# PocketCHIP-v1_0.net
KiCad netlist of a schematic drawn in EAGLE
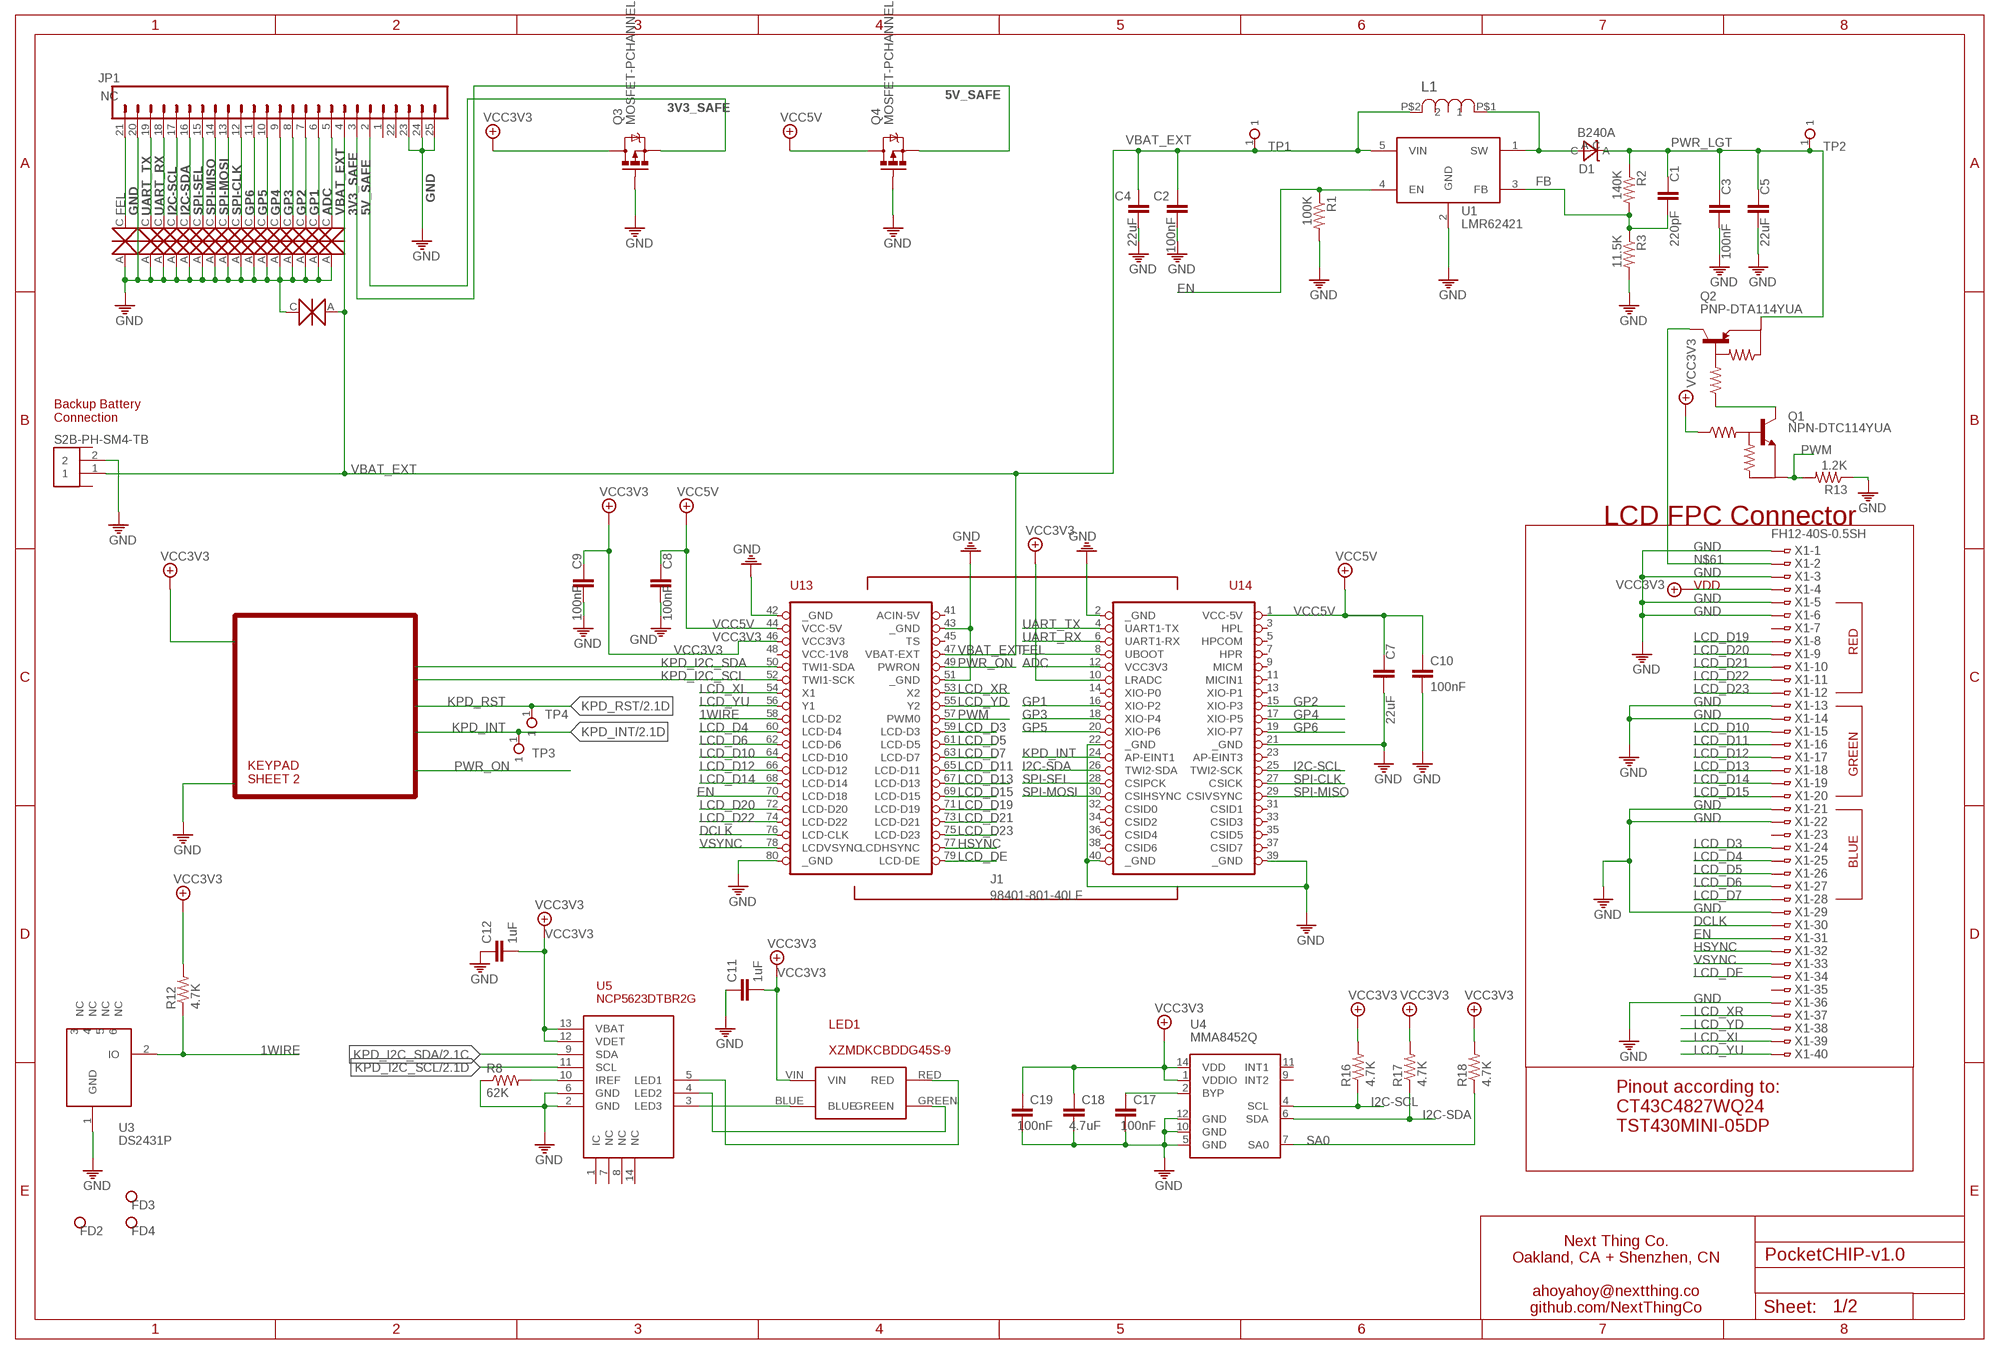
[diagram p0: schematic, sheet 1]
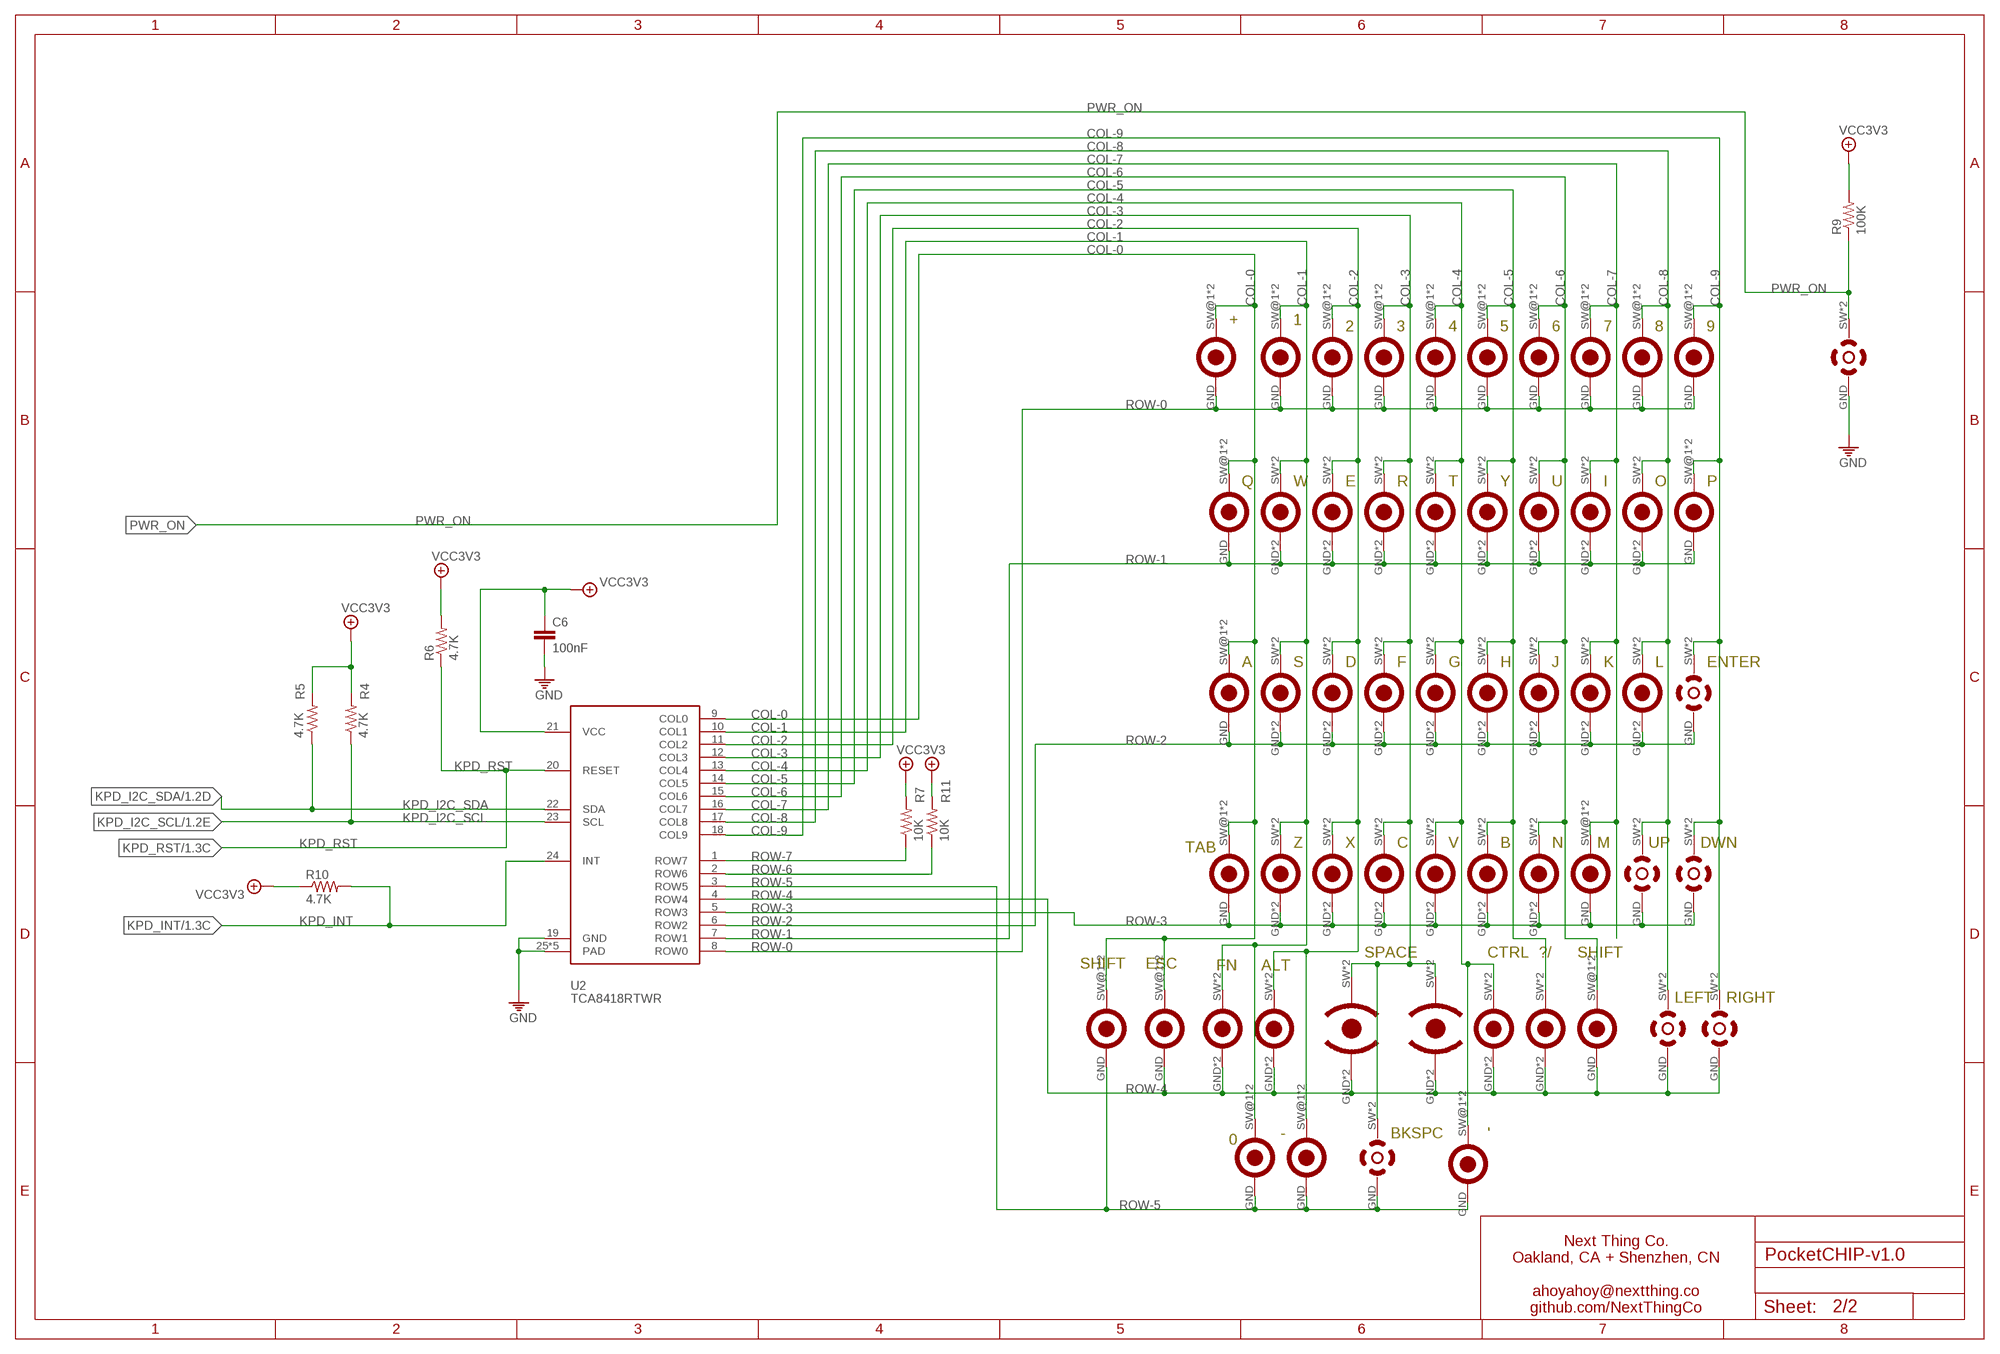
[diagram p1: schematic, sheet 2]

(export (version "E")
  (design (tool "Eeschema 10.0.6"))
  (components
    (comp (ref "'")
      (value "M272201PAD")
      (footprint "eagle-import:SNAPDOME_M27220_1PAD")
      (libsource (lib "eagle-import") (part "M272201PAD"))
    )
    (comp (ref "+")
      (value "M272201PAD")
      (footprint "eagle-import:SNAPDOME_M27220_1PAD")
      (libsource (lib "eagle-import") (part "M272201PAD"))
    )
    (comp (ref "-")
      (value "M272201PAD")
      (footprint "eagle-import:SNAPDOME_M27220_1PAD")
      (libsource (lib "eagle-import") (part "M272201PAD"))
    )
    (comp (ref "0")
      (value "M272201PAD")
      (footprint "eagle-import:SNAPDOME_M27220_1PAD")
      (libsource (lib "eagle-import") (part "M272201PAD"))
    )
    (comp (ref "1")
      (value "M272201PAD")
      (footprint "eagle-import:SNAPDOME_M27220_1PAD")
      (libsource (lib "eagle-import") (part "M272201PAD"))
    )
    (comp (ref "2")
      (value "M272201PAD")
      (footprint "eagle-import:SNAPDOME_M27220_1PAD")
      (libsource (lib "eagle-import") (part "M272201PAD"))
    )
    (comp (ref "3")
      (value "M272201PAD")
      (footprint "eagle-import:SNAPDOME_M27220_1PAD")
      (libsource (lib "eagle-import") (part "M272201PAD"))
    )
    (comp (ref "4")
      (value "M272201PAD")
      (footprint "eagle-import:SNAPDOME_M27220_1PAD")
      (libsource (lib "eagle-import") (part "M272201PAD"))
    )
    (comp (ref "5")
      (value "M272201PAD")
      (footprint "eagle-import:SNAPDOME_M27220_1PAD")
      (libsource (lib "eagle-import") (part "M272201PAD"))
    )
    (comp (ref "6")
      (value "M272201PAD")
      (footprint "eagle-import:SNAPDOME_M27220_1PAD")
      (libsource (lib "eagle-import") (part "M272201PAD"))
    )
    (comp (ref "7")
      (value "M272201PAD")
      (footprint "eagle-import:SNAPDOME_M27220_1PAD")
      (libsource (lib "eagle-import") (part "M272201PAD"))
    )
    (comp (ref "8")
      (value "M272201PAD")
      (footprint "eagle-import:SNAPDOME_M27220_1PAD")
      (libsource (lib "eagle-import") (part "M272201PAD"))
    )
    (comp (ref "9")
      (value "M272201PAD")
      (footprint "eagle-import:SNAPDOME_M27220_1PAD")
      (libsource (lib "eagle-import") (part "M272201PAD"))
    )
    (comp (ref "?/")
      (value "M27220")
      (footprint "eagle-import:SNAPDOME_M27220")
      (libsource (lib "eagle-import") (part "M27220"))
    )
    (comp (ref "A")
      (value "M272201PAD")
      (footprint "eagle-import:SNAPDOME_M27220_1PAD")
      (libsource (lib "eagle-import") (part "M272201PAD"))
    )
    (comp (ref "ALT")
      (value "M27220")
      (footprint "eagle-import:SNAPDOME_M27220")
      (libsource (lib "eagle-import") (part "M27220"))
    )
    (comp (ref "B")
      (value "M27220")
      (footprint "eagle-import:SNAPDOME_M27220")
      (libsource (lib "eagle-import") (part "M27220"))
    )
    (comp (ref "BKSPC")
      (value "BL08260")
      (footprint "eagle-import:SNAPDOME_BL08260")
      (libsource (lib "eagle-import") (part "BL08260"))
    )
    (comp (ref "C")
      (value "M27220")
      (footprint "eagle-import:SNAPDOME_M27220")
      (libsource (lib "eagle-import") (part "M27220"))
    )
    (comp (ref "C6")
      (value "100nF")
      (footprint "eagle-import:C0402")
      (fields (field (name "MFG") "DIGIIKEY") (field (name "VENDOR_PART_NUMBER") "C1005X5R1E104K050BC"))
      (libsource (lib "eagle-import") (part "C0402_100NF_50V_10%"))
    )
    (comp (ref "CTRL")
      (value "M272201PAD")
      (footprint "eagle-import:SNAPDOME_M27220_1PAD")
      (libsource (lib "eagle-import") (part "M272201PAD"))
    )
    (comp (ref "D")
      (value "M27220")
      (footprint "eagle-import:SNAPDOME_M27220")
      (libsource (lib "eagle-import") (part "M27220"))
    )
    (comp (ref "DWN")
      (value "E9-TDF-340")
      (footprint "eagle-import:SNAPDOME_E9-TDF-340")
      (libsource (lib "eagle-import") (part "E9-TDF-340"))
    )
    (comp (ref "E")
      (value "M27220")
      (footprint "eagle-import:SNAPDOME_M27220")
      (libsource (lib "eagle-import") (part "M27220"))
    )
    (comp (ref "ENTER")
      (value "BL08260")
      (footprint "eagle-import:SNAPDOME_BL08260")
      (libsource (lib "eagle-import") (part "BL08260"))
    )
    (comp (ref "ESC")
      (value "M272201PAD")
      (footprint "eagle-import:SNAPDOME_M27220_1PAD")
      (libsource (lib "eagle-import") (part "M272201PAD"))
    )
    (comp (ref "F")
      (value "M27220")
      (footprint "eagle-import:SNAPDOME_M27220")
      (libsource (lib "eagle-import") (part "M27220"))
    )
    (comp (ref "FN")
      (value "M27220")
      (footprint "eagle-import:SNAPDOME_M27220")
      (libsource (lib "eagle-import") (part "M27220"))
    )
    (comp (ref "G")
      (value "M27220")
      (footprint "eagle-import:SNAPDOME_M27220")
      (libsource (lib "eagle-import") (part "M27220"))
    )
    (comp (ref "H")
      (value "M27220")
      (footprint "eagle-import:SNAPDOME_M27220")
      (libsource (lib "eagle-import") (part "M27220"))
    )
    (comp (ref "I")
      (value "M27220")
      (footprint "eagle-import:SNAPDOME_M27220")
      (libsource (lib "eagle-import") (part "M27220"))
    )
    (comp (ref "J")
      (value "M27220")
      (footprint "eagle-import:SNAPDOME_M27220")
      (libsource (lib "eagle-import") (part "M27220"))
    )
    (comp (ref "K")
      (value "M27220")
      (footprint "eagle-import:SNAPDOME_M27220")
      (libsource (lib "eagle-import") (part "M27220"))
    )
    (comp (ref "L")
      (value "M27220")
      (footprint "eagle-import:SNAPDOME_M27220")
      (libsource (lib "eagle-import") (part "M27220"))
    )
    (comp (ref "LEFT")
      (value "E9-TDF-340")
      (footprint "eagle-import:SNAPDOME_E9-TDF-340")
      (libsource (lib "eagle-import") (part "E9-TDF-340"))
    )
    (comp (ref "M")
      (value "M272201PAD")
      (footprint "eagle-import:SNAPDOME_M27220_1PAD")
      (libsource (lib "eagle-import") (part "M272201PAD"))
    )
    (comp (ref "N")
      (value "M27220")
      (footprint "eagle-import:SNAPDOME_M27220")
      (libsource (lib "eagle-import") (part "M27220"))
    )
    (comp (ref "O")
      (value "M27220")
      (footprint "eagle-import:SNAPDOME_M27220")
      (libsource (lib "eagle-import") (part "M27220"))
    )
    (comp (ref "P")
      (value "M272201PAD")
      (footprint "eagle-import:SNAPDOME_M27220_1PAD")
      (libsource (lib "eagle-import") (part "M272201PAD"))
    )
    (comp (ref "PWR")
      (value "100105")
      (footprint "eagle-import:SNAPDOME_100105")
      (libsource (lib "eagle-import") (part "100105"))
    )
    (comp (ref "Q")
      (value "M272201PAD")
      (footprint "eagle-import:SNAPDOME_M27220_1PAD")
      (libsource (lib "eagle-import") (part "M272201PAD"))
    )
    (comp (ref "R")
      (value "M27220")
      (footprint "eagle-import:SNAPDOME_M27220")
      (libsource (lib "eagle-import") (part "M27220"))
    )
    (comp (ref "R4")
      (value "4.7K")
      (footprint "eagle-import:R0402")
      (fields (field (name "MFG") "DIGIKEY") (field (name "VENDOR_PART_NUMBER") "ERJ-2GEJ472X"))
      (libsource (lib "eagle-import") (part "R0402_4K7_5%"))
    )
    (comp (ref "R5")
      (value "4.7K")
      (footprint "eagle-import:R0402")
      (fields (field (name "MFG") "DIGIKEY") (field (name "VENDOR_PART_NUMBER") "ERJ-2GEJ472X"))
      (libsource (lib "eagle-import") (part "R0402_4K7_5%"))
    )
    (comp (ref "R6")
      (value "4.7K")
      (footprint "eagle-import:R0402")
      (fields (field (name "MFG") "DIGIKEY") (field (name "VENDOR_PART_NUMBER") "ERJ-2GEJ102X"))
      (libsource (lib "eagle-import") (part "R0402_1K_5%"))
    )
    (comp (ref "R7")
      (value "10K")
      (footprint "eagle-import:R0402")
      (fields (field (name "MFG") "DIGIKEY") (field (name "VENDOR_PART_NUMBER") "ERJ-2GEJ472X"))
      (libsource (lib "eagle-import") (part "R0402_4K7_5%"))
    )
    (comp (ref "R9")
      (value "100K")
      (footprint "eagle-import:R0402")
      (fields (field (name "MFG") "DIGIKEY") (field (name "VENDOR_PART_NUMBER") "ERJ-2GEJ104X"))
      (libsource (lib "eagle-import") (part "R0402_100K_5%"))
    )
    (comp (ref "R10")
      (value "4.7K")
      (footprint "eagle-import:R0402")
      (fields (field (name "MFG") "DIGIKEY") (field (name "VENDOR_PART_NUMBER") "ERJ-2GEJ102X"))
      (libsource (lib "eagle-import") (part "R0402_1K_5%"))
    )
    (comp (ref "R11")
      (value "10K")
      (footprint "eagle-import:R0402")
      (fields (field (name "MFG") "DIGIKEY") (field (name "VENDOR_PART_NUMBER") "ERJ-2GEJ472X"))
      (libsource (lib "eagle-import") (part "R0402_4K7_5%"))
    )
    (comp (ref "RIGHT")
      (value "E9-TDF-340")
      (footprint "eagle-import:SNAPDOME_E9-TDF-340")
      (libsource (lib "eagle-import") (part "E9-TDF-340"))
    )
    (comp (ref "S")
      (value "M27220")
      (footprint "eagle-import:SNAPDOME_M27220")
      (libsource (lib "eagle-import") (part "M27220"))
    )
    (comp (ref "SHFT")
      (value "M272201PAD")
      (footprint "eagle-import:SNAPDOME_M27220_1PAD")
      (libsource (lib "eagle-import") (part "M272201PAD"))
    )
    (comp (ref "SHIFT")
      (value "M272201PAD")
      (footprint "eagle-import:SNAPDOME_M27220_1PAD")
      (libsource (lib "eagle-import") (part "M272201PAD"))
    )
    (comp (ref "SPACEL")
      (value "E.22-ONN-230")
      (footprint "eagle-import:SNAPDOME_E.22-ONN-230")
      (libsource (lib "eagle-import") (part "E.22-ONN-230"))
    )
    (comp (ref "SPACER")
      (value "E.22-ONN-230")
      (footprint "eagle-import:SNAPDOME_E.22-ONN-230")
      (libsource (lib "eagle-import") (part "E.22-ONN-230"))
    )
    (comp (ref "T")
      (value "M27220")
      (footprint "eagle-import:SNAPDOME_M27220")
      (libsource (lib "eagle-import") (part "M27220"))
    )
    (comp (ref "TAB")
      (value "M27220")
      (footprint "eagle-import:SNAPDOME_M27220")
      (libsource (lib "eagle-import") (part "M27220"))
    )
    (comp (ref "U")
      (value "M27220")
      (footprint "eagle-import:SNAPDOME_M27220")
      (libsource (lib "eagle-import") (part "M27220"))
    )
    (comp (ref "U2")
      (value "TCA8418RTWR")
      (footprint "eagle-import:WQFN24")
      (fields (field (name "MFG") "DIGIKEY"))
      (libsource (lib "eagle-import") (part "TCA8418RTWR"))
    )
    (comp (ref "UP")
      (value "E9-TDF-340")
      (footprint "eagle-import:SNAPDOME_E9-TDF-340")
      (libsource (lib "eagle-import") (part "E9-TDF-340"))
    )
    (comp (ref "V")
      (value "M27220")
      (footprint "eagle-import:SNAPDOME_M27220")
      (libsource (lib "eagle-import") (part "M27220"))
    )
    (comp (ref "W")
      (value "M27220")
      (footprint "eagle-import:SNAPDOME_M27220")
      (libsource (lib "eagle-import") (part "M27220"))
    )
    (comp (ref "X")
      (value "M27220")
      (footprint "eagle-import:SNAPDOME_M27220")
      (libsource (lib "eagle-import") (part "M27220"))
    )
    (comp (ref "Y")
      (value "M27220")
      (footprint "eagle-import:SNAPDOME_M27220")
      (libsource (lib "eagle-import") (part "M27220"))
    )
    (comp (ref "Z")
      (value "M27220")
      (footprint "eagle-import:SNAPDOME_M27220")
      (libsource (lib "eagle-import") (part "M27220"))
    )
    (comp (ref "C1")
      (value "220pF")
      (footprint "eagle-import:C0402")
      (fields (field (name "MFG") "DIGIIKEY") (field (name "VENDOR_PART_NUMBER") "C0402C221J5GACTU"))
      (libsource (lib "eagle-import") (part "C0402_220PF_50V_5%"))
    )
    (comp (ref "C2")
      (value "100nF")
      (footprint "eagle-import:C0402")
      (fields (field (name "MFG") "DIGIIKEY") (field (name "VENDOR_PART_NUMBER") "C1005X5R1E104K050BC"))
      (libsource (lib "eagle-import") (part "C0402_100NF_50V_10%"))
    )
    (comp (ref "C3")
      (value "100nF")
      (footprint "eagle-import:C0402")
      (fields (field (name "MFG") "DIGIIKEY") (field (name "VENDOR_PART_NUMBER") "C1005X5R1E104K050BC"))
      (libsource (lib "eagle-import") (part "C0402_100NF_50V_10%"))
    )
    (comp (ref "C4")
      (value "22uF")
      (footprint "eagle-import:C1206")
      (fields (field (name "MFG") "DIGIKEY") (field (name "VENDOR_PART_NUMBER") "C3216X5R1V226M160AC"))
      (libsource (lib "eagle-import") (part "C1206_22UF_50V_10%"))
    )
    (comp (ref "C5")
      (value "22uF")
      (footprint "eagle-import:C1206")
      (fields (field (name "MFG") "DIGIKEY") (field (name "VENDOR_PART_NUMBER") "C3216X5R1V226M160AC"))
      (libsource (lib "eagle-import") (part "C1206_22UF_50V_10%"))
    )
    (comp (ref "C7")
      (value "22uF")
      (footprint "eagle-import:C1206")
      (fields (field (name "MFG") "DIGIKEY") (field (name "VENDOR_PART_NUMBER") "C3216X5R1V226M160AC"))
      (libsource (lib "eagle-import") (part "C1206_22UF_50V_10%"))
    )
    (comp (ref "C8")
      (value "100nF")
      (footprint "eagle-import:C0402")
      (fields (field (name "MFG") "DIGIIKEY") (field (name "VENDOR_PART_NUMBER") "C1005X5R1E104K050BC"))
      (libsource (lib "eagle-import") (part "C0402_100NF_50V_10%"))
    )
    (comp (ref "C9")
      (value "100nF")
      (footprint "eagle-import:C0402")
      (fields (field (name "MFG") "DIGIIKEY") (field (name "VENDOR_PART_NUMBER") "C1005X5R1E104K050BC"))
      (libsource (lib "eagle-import") (part "C0402_100NF_50V_10%"))
    )
    (comp (ref "C10")
      (value "100nF")
      (footprint "eagle-import:C0402")
      (fields (field (name "MFG") "DIGIIKEY") (field (name "VENDOR_PART_NUMBER") "C1005X5R1E104K050BC"))
      (libsource (lib "eagle-import") (part "C0402_100NF_50V_10%"))
    )
    (comp (ref "C11")
      (value "1uF")
      (footprint "eagle-import:C0402")
      (fields (field (name "MFG") "DIGIIKEY") (field (name "VENDOR_PART_NUMBER") "C1005X5R1E104K050BC"))
      (libsource (lib "eagle-import") (part "C0402_1UF_50V_10%"))
    )
    (comp (ref "C12")
      (value "1uF")
      (footprint "eagle-import:C0402")
      (fields (field (name "MFG") "DIGIIKEY") (field (name "VENDOR_PART_NUMBER") "C1005X5R1E104K050BC"))
      (libsource (lib "eagle-import") (part "C0402_1UF_50V_10%"))
    )
    (comp (ref "C17")
      (value "100nF")
      (footprint "eagle-import:C0402")
      (fields (field (name "MFG") "DIGIIKEY") (field (name "VENDOR_PART_NUMBER") "C1005X5R1E104K050BC"))
      (libsource (lib "eagle-import") (part "PocketCHIP-Components-v0.71_C0402_100NF_50V_10%"))
    )
    (comp (ref "C18")
      (value "4.7uF")
      (footprint "eagle-import:C0402")
      (fields (field (name "MFG") "DIGIIKEY") (field (name "VENDOR_PART_NUMBER") "C1005X5R1E104K050BC"))
      (libsource (lib "eagle-import") (part "PocketCHIP-Components-v0.71_C0402_100NF_50V_10%"))
    )
    (comp (ref "C19")
      (value "100nF")
      (footprint "eagle-import:C0402")
      (fields (field (name "MFG") "DIGIIKEY") (field (name "VENDOR_PART_NUMBER") "C1005X5R1E104K050BC"))
      (libsource (lib "eagle-import") (part "PocketCHIP-Components-v0.71_C0402_100NF_50V_10%"))
    )
    (comp (ref "D1")
      (value "B240A")
      (footprint "eagle-import:DO-214AC")
      (fields (field (name "MFG") "DIGIKEY") (field (name "VENDOR_PART_NUMBER") "B240A-13-F"))
      (libsource (lib "eagle-import") (part "DIODE_SCHTKY_B240"))
    )
    (comp (ref "ESD1")
      (value "ESD5Z2.5T1G")
      (footprint "eagle-import:SOD523")
      (libsource (lib "eagle-import") (part "ESD5Z2.5T1G"))
    )
    (comp (ref "ESD2")
      (value "ESD5Z2.5T1G")
      (footprint "eagle-import:SOD523")
      (libsource (lib "eagle-import") (part "ESD5Z2.5T1G"))
    )
    (comp (ref "ESD3")
      (value "ESD5Z2.5T1G")
      (footprint "eagle-import:SOD523")
      (libsource (lib "eagle-import") (part "ESD5Z2.5T1G"))
    )
    (comp (ref "ESD4")
      (value "ESD5Z2.5T1G")
      (footprint "eagle-import:SOD523")
      (libsource (lib "eagle-import") (part "ESD5Z2.5T1G"))
    )
    (comp (ref "ESD5")
      (value "ESD5Z2.5T1G")
      (footprint "eagle-import:SOD523")
      (libsource (lib "eagle-import") (part "ESD5Z2.5T1G"))
    )
    (comp (ref "ESD6")
      (value "ESD5Z2.5T1G")
      (footprint "eagle-import:SOD523")
      (libsource (lib "eagle-import") (part "ESD5Z2.5T1G"))
    )
    (comp (ref "ESD7")
      (value "ESD5Z2.5T1G")
      (footprint "eagle-import:SOD523")
      (libsource (lib "eagle-import") (part "ESD5Z2.5T1G"))
    )
    (comp (ref "ESD8")
      (value "ESD5Z2.5T1G")
      (footprint "eagle-import:SOD523")
      (libsource (lib "eagle-import") (part "ESD5Z2.5T1G"))
    )
    (comp (ref "ESD9")
      (value "ESD5Z2.5T1G")
      (footprint "eagle-import:SOD523")
      (libsource (lib "eagle-import") (part "ESD5Z2.5T1G"))
    )
    (comp (ref "ESD10")
      (value "ESD5Z2.5T1G")
      (footprint "eagle-import:SOD523")
      (libsource (lib "eagle-import") (part "ESD5Z2.5T1G"))
    )
    (comp (ref "ESD11")
      (value "ESD5Z2.5T1G")
      (footprint "eagle-import:SOD523")
      (libsource (lib "eagle-import") (part "ESD5Z2.5T1G"))
    )
    (comp (ref "ESD12")
      (value "ESD5Z2.5T1G")
      (footprint "eagle-import:SOD523")
      (libsource (lib "eagle-import") (part "ESD5Z2.5T1G"))
    )
    (comp (ref "ESD13")
      (value "ESD5Z2.5T1G")
      (footprint "eagle-import:SOD523")
      (libsource (lib "eagle-import") (part "ESD5Z2.5T1G"))
    )
    (comp (ref "ESD14")
      (value "ESD5Z2.5T1G")
      (footprint "eagle-import:SOD523")
      (libsource (lib "eagle-import") (part "ESD5Z2.5T1G"))
    )
    (comp (ref "ESD15")
      (value "ESD5Z2.5T1G")
      (footprint "eagle-import:SOD523")
      (libsource (lib "eagle-import") (part "ESD5Z2.5T1G"))
    )
    (comp (ref "ESD16")
      (value "ESD5Z2.5T1G")
      (footprint "eagle-import:SOD523")
      (libsource (lib "eagle-import") (part "ESD5Z2.5T1G"))
    )
    (comp (ref "ESD17")
      (value "ESD5Z2.5T1G")
      (footprint "eagle-import:SOD523")
      (libsource (lib "eagle-import") (part "ESD5Z2.5T1G"))
    )
    (comp (ref "FD2")
      (value "FIDUCIAL")
      (footprint "eagle-import:FIDUCIAL_1MM")
      (fields (field (name "PART_NUMBER") "RB00000042"))
      (libsource (lib "eagle-import") (part "FIDUCIAL"))
    )
    (comp (ref "FD3")
      (value "FIDUCIAL")
      (footprint "eagle-import:FIDUCIAL_1MM")
      (fields (field (name "PART_NUMBER") "RB00000042"))
      (libsource (lib "eagle-import") (part "FIDUCIAL"))
    )
    (comp (ref "FD4")
      (value "FIDUCIAL")
      (footprint "eagle-import:FIDUCIAL_1MM")
      (fields (field (name "PART_NUMBER") "RB00000042"))
      (libsource (lib "eagle-import") (part "FIDUCIAL"))
    )
    (comp (ref "J1")
      (value "98401-801-40LF")
      (footprint "eagle-import:98401-801-40LF")
      (libsource (lib "eagle-import") (part "98401-801-40LF"))
    )
    (comp (ref "J3")
      (value "S2B-PH-SM4-TB")
      (footprint "eagle-import:S2B-PH-SM4-TB")
      (fields (field (name "MFG") "DIGIKEY") (field (name "VENDOR_PART_NUMBER") "S2B-PH-SM4-TB(LF)(SN)"))
      (libsource (lib "eagle-import") (part "S2B-PH-SM4-TB"))
    )
    (comp (ref "JP1")
      (value "NC")
      (footprint "eagle-import:1X20_LOCK_LONGPADS")
      (libsource (lib "eagle-import") (part "M20LOCK_LONGPADS"))
    )
    (comp (ref "L1")
      (value "SRN6045-100M")
      (footprint "eagle-import:SRN6045")
      (fields (field (name "MFG") "DIGIKEY"))
      (libsource (lib "eagle-import") (part "SRN6045-100M"))
    )
    (comp (ref "LED1")
      (value "XZMDKCBDDG45S-9")
      (footprint "eagle-import:XZMDKCBDDG45S-9")
      (libsource (lib "eagle-import") (part "XZMDKCBDDG45S-9"))
    )
    (comp (ref "Q1")
      (value "NPN-DTC114YUA")
      (footprint "eagle-import:SOT323")
      (libsource (lib "eagle-import") (part "NPN-DTC114YUA"))
    )
    (comp (ref "Q2")
      (value "PNP-DTA114YUA")
      (footprint "eagle-import:SOT323")
      (libsource (lib "eagle-import") (part "PNP-DTA114YUA"))
    )
    (comp (ref "Q3")
      (value "MOSFET-PCHANNEL")
      (footprint "eagle-import:SOT23-3")
      (libsource (lib "eagle-import") (part "MOSFET-PCHANNEL"))
    )
    (comp (ref "Q4")
      (value "MOSFET-PCHANNEL")
      (footprint "eagle-import:SOT23-3")
      (libsource (lib "eagle-import") (part "MOSFET-PCHANNEL"))
    )
    (comp (ref "R1")
      (value "100K")
      (footprint "eagle-import:R0402")
      (fields (field (name "MFG") "DIGIKEY") (field (name "VENDOR_PART_NUMBER") "ERJ-2GEJ104X"))
      (libsource (lib "eagle-import") (part "R0402_100K_5%"))
    )
    (comp (ref "R2")
      (value "140K")
      (footprint "eagle-import:R0402")
      (fields (field (name "MFG") "DIGIKEY") (field (name "VENDOR_PART_NUMBER") "RC0402FR-07140KL"))
      (libsource (lib "eagle-import") (part "R0402_140K_1%"))
    )
    (comp (ref "R3")
      (value "11.5K")
      (footprint "eagle-import:R0402")
      (fields (field (name "MFG") "DIGIKEY") (field (name "VENDOR_PART_NUMBER") "RC0402FR-0711K5L"))
      (libsource (lib "eagle-import") (part "R0402_11K5_1%"))
    )
    (comp (ref "R8")
      (value "62K")
      (footprint "eagle-import:R0402")
      (fields (field (name "MFG") "DIGIKEY") (field (name "VENDOR_PART_NUMBER") "ERJ-2GEJ102X"))
      (libsource (lib "eagle-import") (part "R0402_62K_5%"))
    )
    (comp (ref "R12")
      (value "4.7K")
      (footprint "eagle-import:R0402")
      (fields (field (name "MFG") "DIGIKEY") (field (name "VENDOR_PART_NUMBER") "ERJ-2GEJ472X"))
      (libsource (lib "eagle-import") (part "R0402_4K7_5%"))
    )
    (comp (ref "R13")
      (value "1.2K")
      (footprint "eagle-import:R0402")
      (fields (field (name "MFG") "DIGIKEY") (field (name "VENDOR_PART_NUMBER") "ERJ-2GEJ102X"))
      (libsource (lib "eagle-import") (part "PocketCHIP-Components-v0.72_R0402_1K_5%"))
    )
    (comp (ref "R16")
      (value "4.7K")
      (footprint "eagle-import:R0402")
      (fields (field (name "MFG") "DIGIKEY") (field (name "VENDOR_PART_NUMBER") "ERJ-2GEJ472X"))
      (libsource (lib "eagle-import") (part "PocketCHIP-Components-v0.71_R0402_4K7_5%"))
    )
    (comp (ref "R17")
      (value "4.7K")
      (footprint "eagle-import:R0402")
      (fields (field (name "MFG") "DIGIKEY") (field (name "VENDOR_PART_NUMBER") "ERJ-2GEJ472X"))
      (libsource (lib "eagle-import") (part "PocketCHIP-Components-v0.71_R0402_4K7_5%"))
    )
    (comp (ref "R18")
      (value "4.7K")
      (footprint "eagle-import:R0402")
      (fields (field (name "MFG") "DIGIKEY") (field (name "VENDOR_PART_NUMBER") "ERJ-2GEJ472X"))
      (libsource (lib "eagle-import") (part "PocketCHIP-Components-v0.71_R0402_4K7_5%"))
    )
    (comp (ref "TP1")
      (value "N.C")
      (footprint "eagle-import:TP_19_5")
      (fields (field (name "PART_NUMBER") "RB00000140"))
      (libsource (lib "eagle-import") (part "PocketCHIP-Components-v0.71_TP_SMD_0_5MM"))
    )
    (comp (ref "TP2")
      (value "N.C")
      (footprint "eagle-import:TP_19_5")
      (fields (field (name "PART_NUMBER") "RB00000140"))
      (libsource (lib "eagle-import") (part "PocketCHIP-Components-v0.71_TP_SMD_0_5MM"))
    )
    (comp (ref "TP3")
      (value "N.C")
      (footprint "eagle-import:TP_19_5")
      (fields (field (name "PART_NUMBER") "RB00000140"))
      (libsource (lib "eagle-import") (part "TP_SMD_0_5MM"))
    )
    (comp (ref "TP4")
      (value "N.C")
      (footprint "eagle-import:TP_19_5")
      (fields (field (name "PART_NUMBER") "RB00000140"))
      (libsource (lib "eagle-import") (part "TP_SMD_0_5MM"))
    )
    (comp (ref "U1")
      (value "LMR62421")
      (footprint "eagle-import:SOT23-5")
      (fields (field (name "MFG") "DIGIKEY") (field (name "VENDOR_PART_NUMBER") "LMR62421XMFE/NOPB"))
      (libsource (lib "eagle-import") (part "LMR62421"))
    )
    (comp (ref "U3")
      (value "DS2431P")
      (footprint "eagle-import:TSOC6")
      (fields (field (name "MFG") "DIGIKEY") (field (name "VENDOR_PART_NUMBER") "DS2431P+T&R"))
      (libsource (lib "eagle-import") (part "DS2431P"))
    )
    (comp (ref "U4")
      (value "MMA8452Q")
      (footprint "eagle-import:QFN-16_0.5MM")
      (libsource (lib "eagle-import") (part "MMA8452Q"))
    )
    (comp (ref "U5")
      (value "NCP5623DTBR2G")
      (footprint "eagle-import:TSSOP14")
      (libsource (lib "eagle-import") (part "NCP5623DTBR2G"))
    )
    (comp (ref "X1")
      (value "FH12-40S-0.5SH")
      (footprint "eagle-import:FH12-40S-0.5SH")
      (fields (field (name "MFG") "DIGIKEY") (field (name "VENDOR_PART_NUMBER") "FH12-40S-0.5SH(55)"))
      (libsource (lib "eagle-import") (part "FH12-40S-0.5SH"))
    )
  )
  (nets
    (net (code "1") (name "1WIRE") (class "Default")
      (node (ref "J1") (pin "58") (pinfunction "LCD-D2_58") (pintype "passive"))
      (node (ref "R12") (pin "1") (pinfunction "1_1") (pintype "passive"))
      (node (ref "U3") (pin "2") (pinfunction "IO_2") (pintype "bidirectional"))
    )
    (net (code "2") (name "3V3_SAFE") (class "Default")
      (node (ref "JP1") (pin "2") (pinfunction "2_2") (pintype "passive"))
      (node (ref "Q3") (pin "2") (pinfunction "S_2") (pintype "passive"))
    )
    (net (code "3") (name "5V_SAFE") (class "Default")
      (node (ref "JP1") (pin "3") (pinfunction "3_3") (pintype "passive"))
      (node (ref "Q4") (pin "2") (pinfunction "S_2") (pintype "passive"))
    )
    (net (code "4") (name "ADC") (class "Default")
      (node (ref "ESD16") (pin "C") (pinfunction "P$2_C") (pintype "bidirectional"))
      (node (ref "J1") (pin "12") (pinfunction "VCC3V3_12") (pintype "passive"))
      (node (ref "JP1") (pin "5") (pinfunction "5_5") (pintype "passive"))
    )
    (net (code "5") (name "COL-0") (class "Default")
      (node (ref "1") (pin "SW@1") (pinfunction "SW_SW@1") (pintype "bidirectional"))
      (node (ref "1") (pin "SW@2") (pinfunction "SW_SW@2") (pintype "bidirectional"))
      (node (ref "A") (pin "SW@1") (pinfunction "SW_SW@1") (pintype "bidirectional"))
      (node (ref "A") (pin "SW@2") (pinfunction "SW_SW@2") (pintype "bidirectional"))
      (node (ref "CTRL") (pin "SW@1") (pinfunction "SW_SW@1") (pintype "bidirectional"))
      (node (ref "CTRL") (pin "SW@2") (pinfunction "SW_SW@2") (pintype "bidirectional"))
      (node (ref "ESC") (pin "SW@1") (pinfunction "SW_SW@1") (pintype "bidirectional"))
      (node (ref "ESC") (pin "SW@2") (pinfunction "SW_SW@2") (pintype "bidirectional"))
      (node (ref "Q") (pin "SW@1") (pinfunction "SW_SW@1") (pintype "bidirectional"))
      (node (ref "Q") (pin "SW@2") (pinfunction "SW_SW@2") (pintype "bidirectional"))
      (node (ref "SHIFT") (pin "SW@1") (pinfunction "SW_SW@1") (pintype "bidirectional"))
      (node (ref "SHIFT") (pin "SW@2") (pinfunction "SW_SW@2") (pintype "bidirectional"))
      (node (ref "U2") (pin "9") (pinfunction "COL0_9") (pintype "bidirectional"))
    )
    (net (code "6") (name "COL-1") (class "Default")
      (node (ref "-") (pin "SW@1") (pinfunction "SW_SW@1") (pintype "bidirectional"))
      (node (ref "-") (pin "SW@2") (pinfunction "SW_SW@2") (pintype "bidirectional"))
      (node (ref "2") (pin "SW@1") (pinfunction "SW_SW@1") (pintype "bidirectional"))
      (node (ref "2") (pin "SW@2") (pinfunction "SW_SW@2") (pintype "bidirectional"))
      (node (ref "FN") (pin "SW") (pinfunction "SW_SW") (pintype "bidirectional"))
      (node (ref "FN") (pin "SW1") (pinfunction "SW_SW1") (pintype "bidirectional"))
      (node (ref "S") (pin "SW") (pinfunction "SW_SW") (pintype "bidirectional"))
      (node (ref "S") (pin "SW1") (pinfunction "SW_SW1") (pintype "bidirectional"))
      (node (ref "U2") (pin "10") (pinfunction "COL1_10") (pintype "bidirectional"))
      (node (ref "W") (pin "SW") (pinfunction "SW_SW") (pintype "bidirectional"))
      (node (ref "W") (pin "SW1") (pinfunction "SW_SW1") (pintype "bidirectional"))
      (node (ref "Z") (pin "SW") (pinfunction "SW_SW") (pintype "bidirectional"))
      (node (ref "Z") (pin "SW1") (pinfunction "SW_SW1") (pintype "bidirectional"))
    )
    (net (code "7") (name "COL-2") (class "Default")
      (node (ref "+") (pin "SW@1") (pinfunction "SW_SW@1") (pintype "bidirectional"))
      (node (ref "+") (pin "SW@2") (pinfunction "SW_SW@2") (pintype "bidirectional"))
      (node (ref "3") (pin "SW@1") (pinfunction "SW_SW@1") (pintype "bidirectional"))
      (node (ref "3") (pin "SW@2") (pinfunction "SW_SW@2") (pintype "bidirectional"))
      (node (ref "ALT") (pin "SW") (pinfunction "SW_SW") (pintype "bidirectional"))
      (node (ref "ALT") (pin "SW1") (pinfunction "SW_SW1") (pintype "bidirectional"))
      (node (ref "D") (pin "SW") (pinfunction "SW_SW") (pintype "bidirectional"))
      (node (ref "D") (pin "SW1") (pinfunction "SW_SW1") (pintype "bidirectional"))
      (node (ref "E") (pin "SW") (pinfunction "SW_SW") (pintype "bidirectional"))
      (node (ref "E") (pin "SW1") (pinfunction "SW_SW1") (pintype "bidirectional"))
      (node (ref "U2") (pin "11") (pinfunction "COL2_11") (pintype "bidirectional"))
      (node (ref "X") (pin "SW") (pinfunction "SW_SW") (pintype "bidirectional"))
      (node (ref "X") (pin "SW1") (pinfunction "SW_SW1") (pintype "bidirectional"))
    )
    (net (code "8") (name "COL-3") (class "Default")
      (node (ref "4") (pin "SW@1") (pinfunction "SW_SW@1") (pintype "bidirectional"))
      (node (ref "4") (pin "SW@2") (pinfunction "SW_SW@2") (pintype "bidirectional"))
      (node (ref "BKSPC") (pin "SW") (pinfunction "SW_SW") (pintype "bidirectional"))
      (node (ref "BKSPC") (pin "SW1") (pinfunction "SW_SW1") (pintype "bidirectional"))
      (node (ref "C") (pin "SW") (pinfunction "SW_SW") (pintype "bidirectional"))
      (node (ref "C") (pin "SW1") (pinfunction "SW_SW1") (pintype "bidirectional"))
      (node (ref "F") (pin "SW") (pinfunction "SW_SW") (pintype "bidirectional"))
      (node (ref "F") (pin "SW1") (pinfunction "SW_SW1") (pintype "bidirectional"))
      (node (ref "R") (pin "SW") (pinfunction "SW_SW") (pintype "bidirectional"))
      (node (ref "R") (pin "SW1") (pinfunction "SW_SW1") (pintype "bidirectional"))
      (node (ref "SPACEL") (pin "SW") (pinfunction "SW_SW") (pintype "bidirectional"))
      (node (ref "SPACEL") (pin "SW1") (pinfunction "SW_SW1") (pintype "bidirectional"))
      (node (ref "SPACER") (pin "SW") (pinfunction "SW_SW") (pintype "bidirectional"))
      (node (ref "SPACER") (pin "SW1") (pinfunction "SW_SW1") (pintype "bidirectional"))
      (node (ref "U2") (pin "12") (pinfunction "COL3_12") (pintype "bidirectional"))
    )
    (net (code "9") (name "COL-4") (class "Default")
      (node (ref "'") (pin "SW@1") (pinfunction "SW_SW@1") (pintype "bidirectional"))
      (node (ref "'") (pin "SW@2") (pinfunction "SW_SW@2") (pintype "bidirectional"))
      (node (ref "5") (pin "SW@1") (pinfunction "SW_SW@1") (pintype "bidirectional"))
      (node (ref "5") (pin "SW@2") (pinfunction "SW_SW@2") (pintype "bidirectional"))
      (node (ref "G") (pin "SW") (pinfunction "SW_SW") (pintype "bidirectional"))
      (node (ref "G") (pin "SW1") (pinfunction "SW_SW1") (pintype "bidirectional"))
      (node (ref "T") (pin "SW") (pinfunction "SW_SW") (pintype "bidirectional"))
      (node (ref "T") (pin "SW1") (pinfunction "SW_SW1") (pintype "bidirectional"))
      (node (ref "TAB") (pin "SW") (pinfunction "SW_SW") (pintype "bidirectional"))
      (node (ref "TAB") (pin "SW1") (pinfunction "SW_SW1") (pintype "bidirectional"))
      (node (ref "U2") (pin "13") (pinfunction "COL4_13") (pintype "bidirectional"))
      (node (ref "V") (pin "SW") (pinfunction "SW_SW") (pintype "bidirectional"))
      (node (ref "V") (pin "SW1") (pinfunction "SW_SW1") (pintype "bidirectional"))
    )
    (net (code "10") (name "COL-5") (class "Default")
      (node (ref "6") (pin "SW@1") (pinfunction "SW_SW@1") (pintype "bidirectional"))
      (node (ref "6") (pin "SW@2") (pinfunction "SW_SW@2") (pintype "bidirectional"))
      (node (ref "?/") (pin "SW") (pinfunction "SW_SW") (pintype "bidirectional"))
      (node (ref "?/") (pin "SW1") (pinfunction "SW_SW1") (pintype "bidirectional"))
      (node (ref "B") (pin "SW") (pinfunction "SW_SW") (pintype "bidirectional"))
      (node (ref "B") (pin "SW1") (pinfunction "SW_SW1") (pintype "bidirectional"))
      (node (ref "H") (pin "SW") (pinfunction "SW_SW") (pintype "bidirectional"))
      (node (ref "H") (pin "SW1") (pinfunction "SW_SW1") (pintype "bidirectional"))
      (node (ref "U2") (pin "14") (pinfunction "COL5_14") (pintype "bidirectional"))
      (node (ref "Y") (pin "SW") (pinfunction "SW_SW") (pintype "bidirectional"))
      (node (ref "Y") (pin "SW1") (pinfunction "SW_SW1") (pintype "bidirectional"))
    )
    (net (code "11") (name "COL-6") (class "Default")
      (node (ref "7") (pin "SW@1") (pinfunction "SW_SW@1") (pintype "bidirectional"))
      (node (ref "7") (pin "SW@2") (pinfunction "SW_SW@2") (pintype "bidirectional"))
      (node (ref "J") (pin "SW") (pinfunction "SW_SW") (pintype "bidirectional"))
      (node (ref "J") (pin "SW1") (pinfunction "SW_SW1") (pintype "bidirectional"))
      (node (ref "N") (pin "SW") (pinfunction "SW_SW") (pintype "bidirectional"))
      (node (ref "N") (pin "SW1") (pinfunction "SW_SW1") (pintype "bidirectional"))
      (node (ref "SHFT") (pin "SW@1") (pinfunction "SW_SW@1") (pintype "bidirectional"))
      (node (ref "SHFT") (pin "SW@2") (pinfunction "SW_SW@2") (pintype "bidirectional"))
      (node (ref "U") (pin "SW") (pinfunction "SW_SW") (pintype "bidirectional"))
      (node (ref "U") (pin "SW1") (pinfunction "SW_SW1") (pintype "bidirectional"))
      (node (ref "U2") (pin "15") (pinfunction "COL6_15") (pintype "bidirectional"))
    )
    (net (code "12") (name "COL-7") (class "Default")
      (node (ref "8") (pin "SW@1") (pinfunction "SW_SW@1") (pintype "bidirectional"))
      (node (ref "8") (pin "SW@2") (pinfunction "SW_SW@2") (pintype "bidirectional"))
      (node (ref "I") (pin "SW") (pinfunction "SW_SW") (pintype "bidirectional"))
      (node (ref "I") (pin "SW1") (pinfunction "SW_SW1") (pintype "bidirectional"))
      (node (ref "K") (pin "SW") (pinfunction "SW_SW") (pintype "bidirectional"))
      (node (ref "K") (pin "SW1") (pinfunction "SW_SW1") (pintype "bidirectional"))
      (node (ref "M") (pin "SW@1") (pinfunction "SW_SW@1") (pintype "bidirectional"))
      (node (ref "M") (pin "SW@2") (pinfunction "SW_SW@2") (pintype "bidirectional"))
      (node (ref "U2") (pin "16") (pinfunction "COL7_16") (pintype "bidirectional"))
    )
    (net (code "13") (name "COL-8") (class "Default")
      (node (ref "9") (pin "SW@1") (pinfunction "SW_SW@1") (pintype "bidirectional"))
      (node (ref "9") (pin "SW@2") (pinfunction "SW_SW@2") (pintype "bidirectional"))
      (node (ref "L") (pin "SW") (pinfunction "SW_SW") (pintype "bidirectional"))
      (node (ref "L") (pin "SW1") (pinfunction "SW_SW1") (pintype "bidirectional"))
      (node (ref "LEFT") (pin "SW") (pinfunction "SW_SW") (pintype "bidirectional"))
      (node (ref "LEFT") (pin "SW1") (pinfunction "SW_SW1") (pintype "bidirectional"))
      (node (ref "O") (pin "SW") (pinfunction "SW_SW") (pintype "bidirectional"))
      (node (ref "O") (pin "SW1") (pinfunction "SW_SW1") (pintype "bidirectional"))
      (node (ref "U2") (pin "17") (pinfunction "COL8_17") (pintype "bidirectional"))
      (node (ref "UP") (pin "SW") (pinfunction "SW_SW") (pintype "bidirectional"))
      (node (ref "UP") (pin "SW1") (pinfunction "SW_SW1") (pintype "bidirectional"))
    )
    (net (code "14") (name "COL-9") (class "Default")
      (node (ref "0") (pin "SW@1") (pinfunction "SW_SW@1") (pintype "bidirectional"))
      (node (ref "0") (pin "SW@2") (pinfunction "SW_SW@2") (pintype "bidirectional"))
      (node (ref "DWN") (pin "SW") (pinfunction "SW_SW") (pintype "bidirectional"))
      (node (ref "DWN") (pin "SW1") (pinfunction "SW_SW1") (pintype "bidirectional"))
      (node (ref "ENTER") (pin "SW") (pinfunction "SW_SW") (pintype "bidirectional"))
      (node (ref "ENTER") (pin "SW1") (pinfunction "SW_SW1") (pintype "bidirectional"))
      (node (ref "P") (pin "SW@1") (pinfunction "SW_SW@1") (pintype "bidirectional"))
      (node (ref "P") (pin "SW@2") (pinfunction "SW_SW@2") (pintype "bidirectional"))
      (node (ref "RIGHT") (pin "SW") (pinfunction "SW_SW") (pintype "bidirectional"))
      (node (ref "RIGHT") (pin "SW1") (pinfunction "SW_SW1") (pintype "bidirectional"))
      (node (ref "U2") (pin "18") (pinfunction "COL9_18") (pintype "bidirectional"))
    )
    (net (code "15") (name "DCLK") (class "Default")
      (node (ref "J1") (pin "76") (pinfunction "LCD-CLK_76") (pintype "passive"))
      (node (ref "X1") (pin "30") (pinfunction "1_30") (pintype "passive"))
    )
    (net (code "16") (name "EN") (class "Default")
      (node (ref "J1") (pin "70") (pinfunction "LCD-D18_70") (pintype "passive"))
      (node (ref "R1") (pin "1") (pinfunction "1_1") (pintype "passive"))
      (node (ref "U1") (pin "4") (pinfunction "EN_4") (pintype "bidirectional"))
      (node (ref "X1") (pin "31") (pinfunction "1_31") (pintype "passive"))
    )
    (net (code "17") (name "FB") (class "Default")
      (node (ref "C1") (pin "2") (pinfunction "2_2") (pintype "passive"))
      (node (ref "R2") (pin "2") (pinfunction "2_2") (pintype "passive"))
      (node (ref "R3") (pin "1") (pinfunction "1_1") (pintype "passive"))
      (node (ref "U1") (pin "3") (pinfunction "FB_3") (pintype "bidirectional"))
    )
    (net (code "18") (name "FEL") (class "Default")
      (node (ref "ESD1") (pin "C") (pinfunction "P$2_C") (pintype "bidirectional"))
      (node (ref "J1") (pin "8") (pinfunction "UBOOT_8") (pintype "passive"))
      (node (ref "JP1") (pin "21") (pinfunction "21_21") (pintype "passive"))
    )
    (net (code "19") (name "GND") (class "Default")
      (node (ref "C10") (pin "2") (pinfunction "2_2") (pintype "passive"))
      (node (ref "C11") (pin "1") (pinfunction "1_1") (pintype "passive"))
      (node (ref "C12") (pin "1") (pinfunction "1_1") (pintype "passive"))
      (node (ref "C17") (pin "2") (pinfunction "2_2") (pintype "passive"))
      (node (ref "C18") (pin "2") (pinfunction "2_2") (pintype "passive"))
      (node (ref "C19") (pin "2") (pinfunction "2_2") (pintype "passive"))
      (node (ref "C2") (pin "2") (pinfunction "2_2") (pintype "passive"))
      (node (ref "C3") (pin "2") (pinfunction "2_2") (pintype "passive"))
      (node (ref "C4") (pin "2") (pinfunction "2_2") (pintype "passive"))
      (node (ref "C5") (pin "2") (pinfunction "2_2") (pintype "passive"))
      (node (ref "C6") (pin "2") (pinfunction "2_2") (pintype "passive"))
      (node (ref "C7") (pin "2") (pinfunction "2_2") (pintype "passive"))
      (node (ref "C8") (pin "2") (pinfunction "2_2") (pintype "passive"))
      (node (ref "C9") (pin "2") (pinfunction "2_2") (pintype "passive"))
      (node (ref "ESD1") (pin "A") (pinfunction "P$1_A") (pintype "bidirectional"))
      (node (ref "ESD10") (pin "A") (pinfunction "P$1_A") (pintype "bidirectional"))
      (node (ref "ESD11") (pin "A") (pinfunction "P$1_A") (pintype "bidirectional"))
      (node (ref "ESD12") (pin "A") (pinfunction "P$1_A") (pintype "bidirectional"))
      (node (ref "ESD13") (pin "A") (pinfunction "P$1_A") (pintype "bidirectional"))
      (node (ref "ESD14") (pin "A") (pinfunction "P$1_A") (pintype "bidirectional"))
      (node (ref "ESD15") (pin "A") (pinfunction "P$1_A") (pintype "bidirectional"))
      (node (ref "ESD16") (pin "A") (pinfunction "P$1_A") (pintype "bidirectional"))
      (node (ref "ESD17") (pin "C") (pinfunction "P$2_C") (pintype "bidirectional"))
      (node (ref "ESD2") (pin "A") (pinfunction "P$1_A") (pintype "bidirectional"))
      (node (ref "ESD3") (pin "A") (pinfunction "P$1_A") (pintype "bidirectional"))
      (node (ref "ESD4") (pin "A") (pinfunction "P$1_A") (pintype "bidirectional"))
      (node (ref "ESD5") (pin "A") (pinfunction "P$1_A") (pintype "bidirectional"))
      (node (ref "ESD6") (pin "A") (pinfunction "P$1_A") (pintype "bidirectional"))
      (node (ref "ESD7") (pin "A") (pinfunction "P$1_A") (pintype "bidirectional"))
      (node (ref "ESD8") (pin "A") (pinfunction "P$1_A") (pintype "bidirectional"))
      (node (ref "ESD9") (pin "A") (pinfunction "P$1_A") (pintype "bidirectional"))
      (node (ref "J1") (pin "2") (pinfunction "_GND_2") (pintype "passive"))
      (node (ref "J1") (pin "21") (pinfunction "_GND_21") (pintype "passive"))
      (node (ref "J1") (pin "22") (pinfunction "_GND_22") (pintype "passive"))
      (node (ref "J1") (pin "39") (pinfunction "_GND_39") (pintype "passive"))
      (node (ref "J1") (pin "40") (pinfunction "_GND_40") (pintype "passive"))
      (node (ref "J1") (pin "42") (pinfunction "_GND_42") (pintype "power_in"))
      (node (ref "J1") (pin "43") (pinfunction "_GND_43") (pintype "passive"))
      (node (ref "J1") (pin "51") (pinfunction "_GND_51") (pintype "passive"))
      (node (ref "J1") (pin "80") (pinfunction "_GND_80") (pintype "power_in"))
      (node (ref "J3") (pin "2") (pinfunction "2_2") (pintype "bidirectional"))
      (node (ref "JP1") (pin "20") (pinfunction "20_20") (pintype "passive"))
      (node (ref "JP1") (pin "23") (pinfunction "23_23") (pintype "passive"))
      (node (ref "JP1") (pin "24") (pinfunction "24_24") (pintype "passive"))
      (node (ref "JP1") (pin "25") (pinfunction "25_25") (pintype "passive"))
      (node (ref "PWR") (pin "GND") (pinfunction "GND_GND") (pintype "bidirectional"))
      (node (ref "Q3") (pin "1") (pinfunction "G_1") (pintype "passive"))
      (node (ref "Q4") (pin "1") (pinfunction "G_1") (pintype "passive"))
      (node (ref "R1") (pin "2") (pinfunction "2_2") (pintype "passive"))
      (node (ref "R13") (pin "1") (pinfunction "1_1") (pintype "passive"))
      (node (ref "R3") (pin "2") (pinfunction "2_2") (pintype "passive"))
      (node (ref "R8") (pin "1") (pinfunction "1_1") (pintype "passive"))
      (node (ref "U1") (pin "2") (pinfunction "GND_2") (pintype "bidirectional"))
      (node (ref "U2") (pin "19") (pinfunction "GND_19") (pintype "power_in"))
      (node (ref "U2") (pin "25") (pinfunction "PAD_25") (pintype "power_in"))
      (node (ref "U2") (pin "H1") (pinfunction "PAD_H1") (pintype "power_in"))
      (node (ref "U2") (pin "H2") (pinfunction "PAD_H2") (pintype "power_in"))
      (node (ref "U2") (pin "H3") (pinfunction "PAD_H3") (pintype "power_in"))
      (node (ref "U2") (pin "H4") (pinfunction "PAD_H4") (pintype "power_in"))
      (node (ref "U3") (pin "1") (pinfunction "GND_1") (pintype "bidirectional"))
      (node (ref "U4") (pin "10") (pinfunction "GND_10") (pintype "bidirectional"))
      (node (ref "U4") (pin "12") (pinfunction "GND_12") (pintype "bidirectional"))
      (node (ref "U4") (pin "5") (pinfunction "GND_5") (pintype "bidirectional"))
      (node (ref "U5") (pin "2") (pinfunction "GND_2") (pintype "bidirectional"))
      (node (ref "U5") (pin "6") (pinfunction "GND_6") (pintype "bidirectional"))
      (node (ref "X1") (pin "1") (pinfunction "1_1") (pintype "passive"))
      (node (ref "X1") (pin "13") (pinfunction "1_13") (pintype "passive"))
      (node (ref "X1") (pin "14") (pinfunction "1_14") (pintype "passive"))
      (node (ref "X1") (pin "21") (pinfunction "1_21") (pintype "passive"))
      (node (ref "X1") (pin "22") (pinfunction "1_22") (pintype "passive"))
      (node (ref "X1") (pin "29") (pinfunction "1_29") (pintype "passive"))
      (node (ref "X1") (pin "3") (pinfunction "1_3") (pintype "passive"))
      (node (ref "X1") (pin "36") (pinfunction "1_36") (pintype "passive"))
      (node (ref "X1") (pin "5") (pinfunction "1_5") (pintype "passive"))
      (node (ref "X1") (pin "6") (pinfunction "1_6") (pintype "passive"))
    )
    (net (code "20") (name "GP1") (class "Default")
      (node (ref "ESD15") (pin "C") (pinfunction "P$2_C") (pintype "bidirectional"))
      (node (ref "J1") (pin "16") (pinfunction "XIO-P2_16") (pintype "passive"))
      (node (ref "JP1") (pin "6") (pinfunction "6_6") (pintype "passive"))
    )
    (net (code "21") (name "GP2") (class "Default")
      (node (ref "ESD14") (pin "C") (pinfunction "P$2_C") (pintype "bidirectional"))
      (node (ref "J1") (pin "15") (pinfunction "XIO-P3_15") (pintype "passive"))
      (node (ref "JP1") (pin "7") (pinfunction "7_7") (pintype "passive"))
    )
    (net (code "22") (name "GP3") (class "Default")
      (node (ref "ESD13") (pin "C") (pinfunction "P$2_C") (pintype "bidirectional"))
      (node (ref "J1") (pin "18") (pinfunction "XIO-P4_18") (pintype "passive"))
      (node (ref "JP1") (pin "8") (pinfunction "8_8") (pintype "passive"))
    )
    (net (code "23") (name "GP4") (class "Default")
      (node (ref "ESD12") (pin "C") (pinfunction "P$2_C") (pintype "bidirectional"))
      (node (ref "J1") (pin "17") (pinfunction "XIO-P5_17") (pintype "passive"))
      (node (ref "JP1") (pin "9") (pinfunction "9_9") (pintype "passive"))
    )
    (net (code "24") (name "GP5") (class "Default")
      (node (ref "ESD11") (pin "C") (pinfunction "P$2_C") (pintype "bidirectional"))
      (node (ref "J1") (pin "20") (pinfunction "XIO-P6_20") (pintype "passive"))
      (node (ref "JP1") (pin "10") (pinfunction "10_10") (pintype "passive"))
    )
    (net (code "25") (name "GP6") (class "Default")
      (node (ref "ESD10") (pin "C") (pinfunction "P$2_C") (pintype "bidirectional"))
      (node (ref "J1") (pin "19") (pinfunction "XIO-P7_19") (pintype "passive"))
      (node (ref "JP1") (pin "11") (pinfunction "11_11") (pintype "passive"))
    )
    (net (code "26") (name "HSYNC") (class "Default")
      (node (ref "J1") (pin "77") (pinfunction "LCDHSYNC_77") (pintype "passive"))
      (node (ref "X1") (pin "32") (pinfunction "1_32") (pintype "passive"))
    )
    (net (code "27") (name "I2C-SCL") (class "Default")
      (node (ref "ESD4") (pin "C") (pinfunction "P$2_C") (pintype "bidirectional"))
      (node (ref "J1") (pin "25") (pinfunction "TWI2-SCK_25") (pintype "passive"))
      (node (ref "JP1") (pin "17") (pinfunction "17_17") (pintype "passive"))
      (node (ref "R16") (pin "1") (pinfunction "1_1") (pintype "passive"))
      (node (ref "U4") (pin "4") (pinfunction "SCL_4") (pintype "bidirectional"))
    )
    (net (code "28") (name "I2C-SDA") (class "Default")
      (node (ref "ESD5") (pin "C") (pinfunction "P$2_C") (pintype "bidirectional"))
      (node (ref "J1") (pin "26") (pinfunction "TWI2-SDA_26") (pintype "passive"))
      (node (ref "JP1") (pin "16") (pinfunction "16_16") (pintype "passive"))
      (node (ref "R17") (pin "1") (pinfunction "1_1") (pintype "passive"))
      (node (ref "U4") (pin "6") (pinfunction "SDA_6") (pintype "bidirectional"))
    )
    (net (code "29") (name "KPD_I2C_SCL") (class "Default")
      (node (ref "J1") (pin "52") (pinfunction "TWI1-SCK_52") (pintype "passive"))
      (node (ref "R4") (pin "1") (pinfunction "1_1") (pintype "passive"))
      (node (ref "U2") (pin "23") (pinfunction "SCL_23") (pintype "bidirectional"))
      (node (ref "U5") (pin "11") (pinfunction "SCL_11") (pintype "bidirectional"))
    )
    (net (code "30") (name "KPD_I2C_SDA") (class "Default")
      (node (ref "J1") (pin "50") (pinfunction "TWI1-SDA_50") (pintype "passive"))
      (node (ref "R5") (pin "1") (pinfunction "1_1") (pintype "passive"))
      (node (ref "U2") (pin "22") (pinfunction "SDA_22") (pintype "bidirectional"))
      (node (ref "U5") (pin "9") (pinfunction "SDA_9") (pintype "bidirectional"))
    )
    (net (code "31") (name "KPD_INT") (class "Default")
      (node (ref "J1") (pin "24") (pinfunction "AP-EINT1_24") (pintype "passive"))
      (node (ref "R10") (pin "2") (pinfunction "2_2") (pintype "passive"))
      (node (ref "TP3") (pin "1") (pinfunction "1_1") (pintype "bidirectional"))
      (node (ref "U2") (pin "24") (pinfunction "INT_24") (pintype "bidirectional"))
    )
    (net (code "32") (name "KPD_RST") (class "Default")
      (node (ref "R6") (pin "1") (pinfunction "1_1") (pintype "passive"))
      (node (ref "TP4") (pin "1") (pinfunction "1_1") (pintype "bidirectional"))
      (node (ref "U2") (pin "20") (pinfunction "RESET_20") (pintype "bidirectional"))
    )
    (net (code "33") (name "LCD_D3") (class "Default")
      (node (ref "J1") (pin "59") (pinfunction "LCD-D3_59") (pintype "passive"))
      (node (ref "X1") (pin "24") (pinfunction "1_24") (pintype "passive"))
    )
    (net (code "34") (name "LCD_D4") (class "Default")
      (node (ref "J1") (pin "60") (pinfunction "LCD-D4_60") (pintype "passive"))
      (node (ref "X1") (pin "25") (pinfunction "1_25") (pintype "passive"))
    )
    (net (code "35") (name "LCD_D5") (class "Default")
      (node (ref "J1") (pin "61") (pinfunction "LCD-D5_61") (pintype "passive"))
      (node (ref "X1") (pin "26") (pinfunction "1_26") (pintype "passive"))
    )
    (net (code "36") (name "LCD_D6") (class "Default")
      (node (ref "J1") (pin "62") (pinfunction "LCD-D6_62") (pintype "passive"))
      (node (ref "X1") (pin "27") (pinfunction "1_27") (pintype "passive"))
    )
    (net (code "37") (name "LCD_D7") (class "Default")
      (node (ref "J1") (pin "63") (pinfunction "LCD-D7_63") (pintype "passive"))
      (node (ref "X1") (pin "28") (pinfunction "1_28") (pintype "passive"))
    )
    (net (code "38") (name "LCD_D10") (class "Default")
      (node (ref "J1") (pin "64") (pinfunction "LCD-D10_64") (pintype "passive"))
      (node (ref "X1") (pin "15") (pinfunction "1_15") (pintype "passive"))
    )
    (net (code "39") (name "LCD_D11") (class "Default")
      (node (ref "J1") (pin "65") (pinfunction "LCD-D11_65") (pintype "passive"))
      (node (ref "X1") (pin "16") (pinfunction "1_16") (pintype "passive"))
    )
    (net (code "40") (name "LCD_D12") (class "Default")
      (node (ref "J1") (pin "66") (pinfunction "LCD-D12_66") (pintype "passive"))
      (node (ref "X1") (pin "17") (pinfunction "1_17") (pintype "passive"))
    )
    (net (code "41") (name "LCD_D13") (class "Default")
      (node (ref "J1") (pin "67") (pinfunction "LCD-D13_67") (pintype "passive"))
      (node (ref "X1") (pin "18") (pinfunction "1_18") (pintype "passive"))
    )
    (net (code "42") (name "LCD_D14") (class "Default")
      (node (ref "J1") (pin "68") (pinfunction "LCD-D14_68") (pintype "passive"))
      (node (ref "X1") (pin "19") (pinfunction "1_19") (pintype "passive"))
    )
    (net (code "43") (name "LCD_D15") (class "Default")
      (node (ref "J1") (pin "69") (pinfunction "LCD-D15_69") (pintype "passive"))
      (node (ref "X1") (pin "20") (pinfunction "1_20") (pintype "passive"))
    )
    (net (code "44") (name "LCD_D19") (class "Default")
      (node (ref "J1") (pin "71") (pinfunction "LCD-D19_71") (pintype "passive"))
      (node (ref "X1") (pin "8") (pinfunction "1_8") (pintype "passive"))
    )
    (net (code "45") (name "LCD_D20") (class "Default")
      (node (ref "J1") (pin "72") (pinfunction "LCD-D20_72") (pintype "passive"))
      (node (ref "X1") (pin "9") (pinfunction "1_9") (pintype "passive"))
    )
    (net (code "46") (name "LCD_D21") (class "Default")
      (node (ref "J1") (pin "73") (pinfunction "LCD-D21_73") (pintype "passive"))
      (node (ref "X1") (pin "10") (pinfunction "1_10") (pintype "passive"))
    )
    (net (code "47") (name "LCD_D22") (class "Default")
      (node (ref "J1") (pin "74") (pinfunction "LCD-D22_74") (pintype "passive"))
      (node (ref "X1") (pin "11") (pinfunction "1_11") (pintype "passive"))
    )
    (net (code "48") (name "LCD_D23") (class "Default")
      (node (ref "J1") (pin "75") (pinfunction "LCD-D23_75") (pintype "passive"))
      (node (ref "X1") (pin "12") (pinfunction "1_12") (pintype "passive"))
    )
    (net (code "49") (name "LCD_DE") (class "Default")
      (node (ref "J1") (pin "79") (pinfunction "LCD-DE_79") (pintype "passive"))
      (node (ref "X1") (pin "34") (pinfunction "1_34") (pintype "passive"))
    )
    (net (code "50") (name "LCD_XL") (class "Default")
      (node (ref "J1") (pin "54") (pinfunction "X1_54") (pintype "passive"))
      (node (ref "X1") (pin "39") (pinfunction "1_39") (pintype "passive"))
    )
    (net (code "51") (name "LCD_XR") (class "Default")
      (node (ref "J1") (pin "53") (pinfunction "X2_53") (pintype "passive"))
      (node (ref "X1") (pin "37") (pinfunction "1_37") (pintype "passive"))
    )
    (net (code "52") (name "LCD_YD") (class "Default")
      (node (ref "J1") (pin "55") (pinfunction "Y2_55") (pintype "passive"))
      (node (ref "X1") (pin "38") (pinfunction "1_38") (pintype "passive"))
    )
    (net (code "53") (name "LCD_YU") (class "Default")
      (node (ref "J1") (pin "56") (pinfunction "Y1_56") (pintype "passive"))
      (node (ref "X1") (pin "40") (pinfunction "1_40") (pintype "passive"))
    )
    (net (code "54") (name "N$61") (class "Default")
      (node (ref "Q2") (pin "3") (pinfunction "OUT_3") (pintype "passive"))
      (node (ref "X1") (pin "2") (pinfunction "1_2") (pintype "passive"))
    )
    (net (code "55") (name "Net-(L1-1)") (class "Default")
      (node (ref "D1") (pin "A") (pinfunction "A_A") (pintype "bidirectional"))
      (node (ref "L1") (pin "P$1") (pinfunction "1_P$1") (pintype "passive"))
      (node (ref "U1") (pin "1") (pinfunction "SW_1") (pintype "bidirectional"))
    )
    (net (code "56") (name "Net-(Q1-OUT)") (class "Default")
      (node (ref "Q1") (pin "3") (pinfunction "OUT_3") (pintype "passive"))
      (node (ref "Q2") (pin "1") (pinfunction "IN_1") (pintype "passive"))
    )
    (net (code "57") (name "Net-(U4-BYP)") (class "Default")
      (node (ref "C17") (pin "1") (pinfunction "1_1") (pintype "passive"))
      (node (ref "U4") (pin "2") (pinfunction "BYP_2") (pintype "bidirectional"))
    )
    (net (code "58") (name "Net-(U5-IREF)") (class "Default")
      (node (ref "R8") (pin "2") (pinfunction "2_2") (pintype "passive"))
      (node (ref "U5") (pin "10") (pinfunction "IREF_10") (pintype "bidirectional"))
    )
    (net (code "59") (name "Net-(U5-LED1)") (class "Default")
      (node (ref "LED1") (pin "RED") (pinfunction "RED_RED") (pintype "bidirectional"))
      (node (ref "U5") (pin "5") (pinfunction "LED1_5") (pintype "bidirectional"))
    )
    (net (code "60") (name "Net-(U5-LED2)") (class "Default")
      (node (ref "LED1") (pin "GREEN") (pinfunction "GREEN_GREEN") (pintype "bidirectional"))
      (node (ref "U5") (pin "4") (pinfunction "LED2_4") (pintype "bidirectional"))
    )
    (net (code "61") (name "Net-(U5-LED3)") (class "Default")
      (node (ref "LED1") (pin "BLUE") (pinfunction "BLUE_BLUE") (pintype "bidirectional"))
      (node (ref "U5") (pin "3") (pinfunction "LED3_3") (pintype "bidirectional"))
    )
    (net (code "62") (name "PWM") (class "Default")
      (node (ref "J1") (pin "57") (pinfunction "PWM0_57") (pintype "passive"))
      (node (ref "Q1") (pin "2") (pinfunction "GND_2") (pintype "passive"))
      (node (ref "R13") (pin "2") (pinfunction "2_2") (pintype "passive"))
    )
    (net (code "63") (name "PWR_LGT") (class "Default")
      (node (ref "C1") (pin "1") (pinfunction "1_1") (pintype "passive"))
      (node (ref "C3") (pin "1") (pinfunction "1_1") (pintype "passive"))
      (node (ref "C5") (pin "1") (pinfunction "1_1") (pintype "passive"))
      (node (ref "D1") (pin "C") (pinfunction "C_C") (pintype "bidirectional"))
      (node (ref "Q2") (pin "2") (pinfunction "GND_2") (pintype "passive"))
      (node (ref "R2") (pin "1") (pinfunction "1_1") (pintype "passive"))
      (node (ref "TP2") (pin "1") (pinfunction "1_1") (pintype "bidirectional"))
    )
    (net (code "64") (name "PWR_ON") (class "Default")
      (node (ref "J1") (pin "49") (pinfunction "PWRON_49") (pintype "passive"))
      (node (ref "PWR") (pin "SW") (pinfunction "SW_SW") (pintype "bidirectional"))
      (node (ref "PWR") (pin "SW1") (pinfunction "SW_SW1") (pintype "bidirectional"))
      (node (ref "R9") (pin "1") (pinfunction "1_1") (pintype "passive"))
    )
    (net (code "65") (name "ROW-0") (class "Default")
      (node (ref "0") (pin "GND") (pinfunction "GND_GND") (pintype "bidirectional"))
      (node (ref "1") (pin "GND") (pinfunction "GND_GND") (pintype "bidirectional"))
      (node (ref "2") (pin "GND") (pinfunction "GND_GND") (pintype "bidirectional"))
      (node (ref "3") (pin "GND") (pinfunction "GND_GND") (pintype "bidirectional"))
      (node (ref "4") (pin "GND") (pinfunction "GND_GND") (pintype "bidirectional"))
      (node (ref "5") (pin "GND") (pinfunction "GND_GND") (pintype "bidirectional"))
      (node (ref "6") (pin "GND") (pinfunction "GND_GND") (pintype "bidirectional"))
      (node (ref "7") (pin "GND") (pinfunction "GND_GND") (pintype "bidirectional"))
      (node (ref "8") (pin "GND") (pinfunction "GND_GND") (pintype "bidirectional"))
      (node (ref "9") (pin "GND") (pinfunction "GND_GND") (pintype "bidirectional"))
      (node (ref "U2") (pin "8") (pinfunction "ROW0_8") (pintype "bidirectional"))
    )
    (net (code "66") (name "ROW-1") (class "Default")
      (node (ref "E") (pin "GND") (pinfunction "GND_GND") (pintype "bidirectional"))
      (node (ref "E") (pin "GND@1") (pinfunction "GND_GND@1") (pintype "bidirectional"))
      (node (ref "I") (pin "GND") (pinfunction "GND_GND") (pintype "bidirectional"))
      (node (ref "I") (pin "GND@1") (pinfunction "GND_GND@1") (pintype "bidirectional"))
      (node (ref "O") (pin "GND") (pinfunction "GND_GND") (pintype "bidirectional"))
      (node (ref "O") (pin "GND@1") (pinfunction "GND_GND@1") (pintype "bidirectional"))
      (node (ref "P") (pin "GND") (pinfunction "GND_GND") (pintype "bidirectional"))
      (node (ref "Q") (pin "GND") (pinfunction "GND_GND") (pintype "bidirectional"))
      (node (ref "R") (pin "GND") (pinfunction "GND_GND") (pintype "bidirectional"))
      (node (ref "R") (pin "GND@1") (pinfunction "GND_GND@1") (pintype "bidirectional"))
      (node (ref "T") (pin "GND") (pinfunction "GND_GND") (pintype "bidirectional"))
      (node (ref "T") (pin "GND@1") (pinfunction "GND_GND@1") (pintype "bidirectional"))
      (node (ref "U") (pin "GND") (pinfunction "GND_GND") (pintype "bidirectional"))
      (node (ref "U") (pin "GND@1") (pinfunction "GND_GND@1") (pintype "bidirectional"))
      (node (ref "U2") (pin "7") (pinfunction "ROW1_7") (pintype "bidirectional"))
      (node (ref "W") (pin "GND") (pinfunction "GND_GND") (pintype "bidirectional"))
      (node (ref "W") (pin "GND@1") (pinfunction "GND_GND@1") (pintype "bidirectional"))
      (node (ref "Y") (pin "GND") (pinfunction "GND_GND") (pintype "bidirectional"))
      (node (ref "Y") (pin "GND@1") (pinfunction "GND_GND@1") (pintype "bidirectional"))
    )
    (net (code "67") (name "ROW-2") (class "Default")
      (node (ref "A") (pin "GND") (pinfunction "GND_GND") (pintype "bidirectional"))
      (node (ref "D") (pin "GND") (pinfunction "GND_GND") (pintype "bidirectional"))
      (node (ref "D") (pin "GND@1") (pinfunction "GND_GND@1") (pintype "bidirectional"))
      (node (ref "ENTER") (pin "GND") (pinfunction "GND_GND") (pintype "bidirectional"))
      (node (ref "F") (pin "GND") (pinfunction "GND_GND") (pintype "bidirectional"))
      (node (ref "F") (pin "GND@1") (pinfunction "GND_GND@1") (pintype "bidirectional"))
      (node (ref "G") (pin "GND") (pinfunction "GND_GND") (pintype "bidirectional"))
      (node (ref "G") (pin "GND@1") (pinfunction "GND_GND@1") (pintype "bidirectional"))
      (node (ref "H") (pin "GND") (pinfunction "GND_GND") (pintype "bidirectional"))
      (node (ref "H") (pin "GND@1") (pinfunction "GND_GND@1") (pintype "bidirectional"))
      (node (ref "J") (pin "GND") (pinfunction "GND_GND") (pintype "bidirectional"))
      (node (ref "J") (pin "GND@1") (pinfunction "GND_GND@1") (pintype "bidirectional"))
      (node (ref "K") (pin "GND") (pinfunction "GND_GND") (pintype "bidirectional"))
      (node (ref "K") (pin "GND@1") (pinfunction "GND_GND@1") (pintype "bidirectional"))
      (node (ref "L") (pin "GND") (pinfunction "GND_GND") (pintype "bidirectional"))
      (node (ref "L") (pin "GND@1") (pinfunction "GND_GND@1") (pintype "bidirectional"))
      (node (ref "S") (pin "GND") (pinfunction "GND_GND") (pintype "bidirectional"))
      (node (ref "S") (pin "GND@1") (pinfunction "GND_GND@1") (pintype "bidirectional"))
      (node (ref "U2") (pin "6") (pinfunction "ROW2_6") (pintype "bidirectional"))
    )
    (net (code "68") (name "ROW-3") (class "Default")
      (node (ref "B") (pin "GND") (pinfunction "GND_GND") (pintype "bidirectional"))
      (node (ref "B") (pin "GND@1") (pinfunction "GND_GND@1") (pintype "bidirectional"))
      (node (ref "C") (pin "GND") (pinfunction "GND_GND") (pintype "bidirectional"))
      (node (ref "C") (pin "GND@1") (pinfunction "GND_GND@1") (pintype "bidirectional"))
      (node (ref "DWN") (pin "GND") (pinfunction "GND_GND") (pintype "bidirectional"))
      (node (ref "M") (pin "GND") (pinfunction "GND_GND") (pintype "bidirectional"))
      (node (ref "N") (pin "GND") (pinfunction "GND_GND") (pintype "bidirectional"))
      (node (ref "N") (pin "GND@1") (pinfunction "GND_GND@1") (pintype "bidirectional"))
      (node (ref "SHIFT") (pin "GND") (pinfunction "GND_GND") (pintype "bidirectional"))
      (node (ref "U2") (pin "5") (pinfunction "ROW3_5") (pintype "bidirectional"))
      (node (ref "UP") (pin "GND") (pinfunction "GND_GND") (pintype "bidirectional"))
      (node (ref "V") (pin "GND") (pinfunction "GND_GND") (pintype "bidirectional"))
      (node (ref "V") (pin "GND@1") (pinfunction "GND_GND@1") (pintype "bidirectional"))
      (node (ref "X") (pin "GND") (pinfunction "GND_GND") (pintype "bidirectional"))
      (node (ref "X") (pin "GND@1") (pinfunction "GND_GND@1") (pintype "bidirectional"))
      (node (ref "Z") (pin "GND") (pinfunction "GND_GND") (pintype "bidirectional"))
      (node (ref "Z") (pin "GND@1") (pinfunction "GND_GND@1") (pintype "bidirectional"))
    )
    (net (code "69") (name "ROW-4") (class "Default")
      (node (ref "?/") (pin "GND") (pinfunction "GND_GND") (pintype "bidirectional"))
      (node (ref "?/") (pin "GND@1") (pinfunction "GND_GND@1") (pintype "bidirectional"))
      (node (ref "ALT") (pin "GND") (pinfunction "GND_GND") (pintype "bidirectional"))
      (node (ref "ALT") (pin "GND@1") (pinfunction "GND_GND@1") (pintype "bidirectional"))
      (node (ref "ESC") (pin "GND") (pinfunction "GND_GND") (pintype "bidirectional"))
      (node (ref "FN") (pin "GND") (pinfunction "GND_GND") (pintype "bidirectional"))
      (node (ref "FN") (pin "GND@1") (pinfunction "GND_GND@1") (pintype "bidirectional"))
      (node (ref "LEFT") (pin "GND") (pinfunction "GND_GND") (pintype "bidirectional"))
      (node (ref "RIGHT") (pin "GND") (pinfunction "GND_GND") (pintype "bidirectional"))
      (node (ref "SHFT") (pin "GND") (pinfunction "GND_GND") (pintype "bidirectional"))
      (node (ref "SPACEL") (pin "GND") (pinfunction "GND_GND") (pintype "bidirectional"))
      (node (ref "SPACEL") (pin "GND@1") (pinfunction "GND_GND@1") (pintype "bidirectional"))
      (node (ref "SPACER") (pin "GND") (pinfunction "GND_GND") (pintype "bidirectional"))
      (node (ref "SPACER") (pin "GND@1") (pinfunction "GND_GND@1") (pintype "bidirectional"))
      (node (ref "TAB") (pin "GND") (pinfunction "GND_GND") (pintype "bidirectional"))
      (node (ref "TAB") (pin "GND@1") (pinfunction "GND_GND@1") (pintype "bidirectional"))
      (node (ref "U2") (pin "4") (pinfunction "ROW4_4") (pintype "bidirectional"))
    )
    (net (code "70") (name "ROW-5") (class "Default")
      (node (ref "'") (pin "GND") (pinfunction "GND_GND") (pintype "bidirectional"))
      (node (ref "+") (pin "GND") (pinfunction "GND_GND") (pintype "bidirectional"))
      (node (ref "-") (pin "GND") (pinfunction "GND_GND") (pintype "bidirectional"))
      (node (ref "BKSPC") (pin "GND") (pinfunction "GND_GND") (pintype "bidirectional"))
      (node (ref "CTRL") (pin "GND") (pinfunction "GND_GND") (pintype "bidirectional"))
      (node (ref "U2") (pin "3") (pinfunction "ROW5_3") (pintype "bidirectional"))
    )
    (net (code "71") (name "ROW-6") (class "Default")
      (node (ref "R11") (pin "1") (pinfunction "1_1") (pintype "passive"))
      (node (ref "U2") (pin "2") (pinfunction "ROW6_2") (pintype "bidirectional"))
    )
    (net (code "72") (name "ROW-7") (class "Default")
      (node (ref "R7") (pin "1") (pinfunction "1_1") (pintype "passive"))
      (node (ref "U2") (pin "1") (pinfunction "ROW7_1") (pintype "bidirectional"))
    )
    (net (code "73") (name "SA0") (class "Default")
      (node (ref "R18") (pin "1") (pinfunction "1_1") (pintype "passive"))
      (node (ref "U4") (pin "7") (pinfunction "SA0_7") (pintype "bidirectional"))
    )
    (net (code "74") (name "SPI-CLK") (class "Default")
      (node (ref "ESD9") (pin "C") (pinfunction "P$2_C") (pintype "bidirectional"))
      (node (ref "J1") (pin "27") (pinfunction "CSICK_27") (pintype "passive"))
      (node (ref "JP1") (pin "12") (pinfunction "12_12") (pintype "passive"))
    )
    (net (code "75") (name "SPI-MISO") (class "Default")
      (node (ref "ESD7") (pin "C") (pinfunction "P$2_C") (pintype "bidirectional"))
      (node (ref "J1") (pin "29") (pinfunction "CSIVSYNC_29") (pintype "passive"))
      (node (ref "JP1") (pin "14") (pinfunction "14_14") (pintype "passive"))
    )
    (net (code "76") (name "SPI-MOSI") (class "Default")
      (node (ref "ESD8") (pin "C") (pinfunction "P$2_C") (pintype "bidirectional"))
      (node (ref "J1") (pin "30") (pinfunction "CSIHSYNC_30") (pintype "passive"))
      (node (ref "JP1") (pin "13") (pinfunction "13_13") (pintype "passive"))
    )
    (net (code "77") (name "SPI-SEL") (class "Default")
      (node (ref "ESD6") (pin "C") (pinfunction "P$2_C") (pintype "bidirectional"))
      (node (ref "J1") (pin "28") (pinfunction "CSIPCK_28") (pintype "passive"))
      (node (ref "JP1") (pin "15") (pinfunction "15_15") (pintype "passive"))
    )
    (net (code "78") (name "UART_RX") (class "Default")
      (node (ref "ESD3") (pin "C") (pinfunction "P$2_C") (pintype "bidirectional"))
      (node (ref "J1") (pin "6") (pinfunction "UART1-RX_6") (pintype "passive"))
      (node (ref "JP1") (pin "18") (pinfunction "18_18") (pintype "passive"))
    )
    (net (code "79") (name "UART_TX") (class "Default")
      (node (ref "ESD2") (pin "C") (pinfunction "P$2_C") (pintype "bidirectional"))
      (node (ref "J1") (pin "4") (pinfunction "UART1-TX_4") (pintype "passive"))
      (node (ref "JP1") (pin "19") (pinfunction "19_19") (pintype "passive"))
    )
    (net (code "80") (name "VBAT_EXT") (class "Default")
      (node (ref "C2") (pin "1") (pinfunction "1_1") (pintype "passive"))
      (node (ref "C4") (pin "1") (pinfunction "1_1") (pintype "passive"))
      (node (ref "ESD17") (pin "A") (pinfunction "P$1_A") (pintype "bidirectional"))
      (node (ref "J1") (pin "47") (pinfunction "VBAT-EXT_47") (pintype "passive"))
      (node (ref "J3") (pin "1") (pinfunction "1_1") (pintype "bidirectional"))
      (node (ref "JP1") (pin "4") (pinfunction "4_4") (pintype "passive"))
      (node (ref "L1") (pin "P$2") (pinfunction "2_P$2") (pintype "passive"))
      (node (ref "TP1") (pin "1") (pinfunction "1_1") (pintype "bidirectional"))
      (node (ref "U1") (pin "5") (pinfunction "VIN_5") (pintype "bidirectional"))
    )
    (net (code "81") (name "VCC3V3") (class "Default")
      (node (ref "C11") (pin "2") (pinfunction "2_2") (pintype "passive"))
      (node (ref "C12") (pin "2") (pinfunction "2_2") (pintype "passive"))
      (node (ref "C18") (pin "1") (pinfunction "1_1") (pintype "passive"))
      (node (ref "C19") (pin "1") (pinfunction "1_1") (pintype "passive"))
      (node (ref "C6") (pin "1") (pinfunction "1_1") (pintype "passive"))
      (node (ref "C9") (pin "1") (pinfunction "1_1") (pintype "passive"))
      (node (ref "J1") (pin "10") (pinfunction "LRADC_10") (pintype "passive"))
      (node (ref "J1") (pin "46") (pinfunction "VCC3V3_46") (pintype "bidirectional"))
      (node (ref "LED1") (pin "VIN") (pinfunction "VIN_VIN") (pintype "bidirectional"))
      (node (ref "Q1") (pin "1") (pinfunction "IN_1") (pintype "passive"))
      (node (ref "Q3") (pin "3") (pinfunction "D_3") (pintype "passive"))
      (node (ref "R10") (pin "1") (pinfunction "1_1") (pintype "passive"))
      (node (ref "R11") (pin "2") (pinfunction "2_2") (pintype "passive"))
      (node (ref "R12") (pin "2") (pinfunction "2_2") (pintype "passive"))
      (node (ref "R16") (pin "2") (pinfunction "2_2") (pintype "passive"))
      (node (ref "R17") (pin "2") (pinfunction "2_2") (pintype "passive"))
      (node (ref "R18") (pin "2") (pinfunction "2_2") (pintype "passive"))
      (node (ref "R4") (pin "2") (pinfunction "2_2") (pintype "passive"))
      (node (ref "R5") (pin "2") (pinfunction "2_2") (pintype "passive"))
      (node (ref "R6") (pin "2") (pinfunction "2_2") (pintype "passive"))
      (node (ref "R7") (pin "2") (pinfunction "2_2") (pintype "passive"))
      (node (ref "R9") (pin "2") (pinfunction "2_2") (pintype "passive"))
      (node (ref "U2") (pin "21") (pinfunction "VCC_21") (pintype "power_in"))
      (node (ref "U4") (pin "1") (pinfunction "VDDIO_1") (pintype "bidirectional"))
      (node (ref "U4") (pin "14") (pinfunction "VDD_14") (pintype "bidirectional"))
      (node (ref "U5") (pin "12") (pinfunction "VDET_12") (pintype "bidirectional"))
      (node (ref "U5") (pin "13") (pinfunction "VBAT_13") (pintype "bidirectional"))
      (node (ref "X1") (pin "4") (pinfunction "1_4") (pintype "passive"))
    )
    (net (code "82") (name "VCC5V") (class "Default")
      (node (ref "C10") (pin "1") (pinfunction "1_1") (pintype "passive"))
      (node (ref "C7") (pin "1") (pinfunction "1_1") (pintype "passive"))
      (node (ref "C8") (pin "1") (pinfunction "1_1") (pintype "passive"))
      (node (ref "J1") (pin "1") (pinfunction "VCC-5V_1") (pintype "passive"))
      (node (ref "J1") (pin "44") (pinfunction "VCC-5V_44") (pintype "bidirectional"))
      (node (ref "Q4") (pin "3") (pinfunction "D_3") (pintype "passive"))
    )
    (net (code "83") (name "VSYNC") (class "Default")
      (node (ref "J1") (pin "78") (pinfunction "LCDVSYNC_78") (pintype "passive"))
      (node (ref "X1") (pin "33") (pinfunction "1_33") (pintype "passive"))
    )
    (net (code "84") (name "unconnected-(J1-ACIN-5V-Pad41)") (class "Default")
      (node (ref "J1") (pin "41") (pinfunction "ACIN-5V_41") (pintype "passive"))
    )
    (net (code "85") (name "unconnected-(J1-AP-EINT3-Pad23)") (class "Default")
      (node (ref "J1") (pin "23") (pinfunction "AP-EINT3_23") (pintype "passive"))
    )
    (net (code "86") (name "unconnected-(J1-CSID0-Pad32)") (class "Default")
      (node (ref "J1") (pin "32") (pinfunction "CSID0_32") (pintype "passive"))
    )
    (net (code "87") (name "unconnected-(J1-CSID1-Pad31)") (class "Default")
      (node (ref "J1") (pin "31") (pinfunction "CSID1_31") (pintype "passive"))
    )
    (net (code "88") (name "unconnected-(J1-CSID2-Pad34)") (class "Default")
      (node (ref "J1") (pin "34") (pinfunction "CSID2_34") (pintype "passive"))
    )
    (net (code "89") (name "unconnected-(J1-CSID3-Pad33)") (class "Default")
      (node (ref "J1") (pin "33") (pinfunction "CSID3_33") (pintype "passive"))
    )
    (net (code "90") (name "unconnected-(J1-CSID4-Pad36)") (class "Default")
      (node (ref "J1") (pin "36") (pinfunction "CSID4_36") (pintype "passive"))
    )
    (net (code "91") (name "unconnected-(J1-CSID5-Pad35)") (class "Default")
      (node (ref "J1") (pin "35") (pinfunction "CSID5_35") (pintype "passive"))
    )
    (net (code "92") (name "unconnected-(J1-CSID6-Pad38)") (class "Default")
      (node (ref "J1") (pin "38") (pinfunction "CSID6_38") (pintype "passive"))
    )
    (net (code "93") (name "unconnected-(J1-CSID7-Pad37)") (class "Default")
      (node (ref "J1") (pin "37") (pinfunction "CSID7_37") (pintype "passive"))
    )
    (net (code "94") (name "unconnected-(J1-HPCOM-Pad5)") (class "Default")
      (node (ref "J1") (pin "5") (pinfunction "HPCOM_5") (pintype "passive"))
    )
    (net (code "95") (name "unconnected-(J1-HPL-Pad3)") (class "Default")
      (node (ref "J1") (pin "3") (pinfunction "HPL_3") (pintype "passive"))
    )
    (net (code "96") (name "unconnected-(J1-HPR-Pad7)") (class "Default")
      (node (ref "J1") (pin "7") (pinfunction "HPR_7") (pintype "passive"))
    )
    (net (code "97") (name "unconnected-(J1-MICIN1-Pad11)") (class "Default")
      (node (ref "J1") (pin "11") (pinfunction "MICIN1_11") (pintype "passive"))
    )
    (net (code "98") (name "unconnected-(J1-MICM-Pad9)") (class "Default")
      (node (ref "J1") (pin "9") (pinfunction "MICM_9") (pintype "passive"))
    )
    (net (code "99") (name "unconnected-(J1-TS-Pad45)") (class "Default")
      (node (ref "J1") (pin "45") (pinfunction "TS_45") (pintype "passive"))
    )
    (net (code "100") (name "unconnected-(J1-VCC-1V8-Pad48)") (class "Default")
      (node (ref "J1") (pin "48") (pinfunction "VCC-1V8_48") (pintype "bidirectional"))
    )
    (net (code "101") (name "unconnected-(J1-XIO-P0-Pad14)") (class "Default")
      (node (ref "J1") (pin "14") (pinfunction "XIO-P0_14") (pintype "passive"))
    )
    (net (code "102") (name "unconnected-(J1-XIO-P1-Pad13)") (class "Default")
      (node (ref "J1") (pin "13") (pinfunction "XIO-P1_13") (pintype "passive"))
    )
    (net (code "103") (name "unconnected-(J3-PadMNT1)") (class "Default")
      (node (ref "J3") (pin "MNT1") (pinfunction "MNT1_MNT1") (pintype "no_connect"))
    )
    (net (code "104") (name "unconnected-(J3-PadMNT2)") (class "Default")
      (node (ref "J3") (pin "MNT2") (pinfunction "MNT2_MNT2") (pintype "no_connect"))
    )
    (net (code "105") (name "unconnected-(JP1-Pad1)") (class "Default")
      (node (ref "JP1") (pin "1") (pinfunction "1_1") (pintype "passive"))
    )
    (net (code "106") (name "unconnected-(JP1-Pad22)") (class "Default")
      (node (ref "JP1") (pin "22") (pinfunction "22_22") (pintype "passive"))
    )
    (net (code "107") (name "unconnected-(U3-NC-Pad3)") (class "Default")
      (node (ref "U3") (pin "3") (pinfunction "NC_3") (pintype "bidirectional"))
    )
    (net (code "108") (name "unconnected-(U3-NC-Pad4)") (class "Default")
      (node (ref "U3") (pin "4") (pinfunction "NC_4") (pintype "bidirectional"))
    )
    (net (code "109") (name "unconnected-(U3-NC-Pad5)") (class "Default")
      (node (ref "U3") (pin "5") (pinfunction "NC_5") (pintype "bidirectional"))
    )
    (net (code "110") (name "unconnected-(U3-NC-Pad6)") (class "Default")
      (node (ref "U3") (pin "6") (pinfunction "NC_6") (pintype "bidirectional"))
    )
    (net (code "111") (name "unconnected-(U4-INT1-Pad11)") (class "Default")
      (node (ref "U4") (pin "11") (pinfunction "INT1_11") (pintype "bidirectional"))
    )
    (net (code "112") (name "unconnected-(U4-INT2-Pad9)") (class "Default")
      (node (ref "U4") (pin "9") (pinfunction "INT2_9") (pintype "bidirectional"))
    )
    (net (code "113") (name "unconnected-(U5-IC-Pad1)") (class "Default")
      (node (ref "U5") (pin "1") (pinfunction "IC_1") (pintype "bidirectional"))
    )
    (net (code "114") (name "unconnected-(U5-NC-Pad7)") (class "Default")
      (node (ref "U5") (pin "7") (pinfunction "NC_7") (pintype "bidirectional"))
    )
    (net (code "115") (name "unconnected-(U5-NC-Pad8)") (class "Default")
      (node (ref "U5") (pin "8") (pinfunction "NC_8") (pintype "bidirectional"))
    )
    (net (code "116") (name "unconnected-(U5-NC-Pad14)") (class "Default")
      (node (ref "U5") (pin "14") (pinfunction "NC_14") (pintype "bidirectional"))
    )
    (net (code "117") (name "unconnected-(X1AC-1-Pad35)") (class "Default")
      (node (ref "X1") (pin "35") (pinfunction "1_35") (pintype "passive"))
    )
    (net (code "118") (name "unconnected-(X1AL-1-Pad7)") (class "Default")
      (node (ref "X1") (pin "7") (pinfunction "1_7") (pintype "passive"))
    )
    (net (code "119") (name "unconnected-(X1P-1-Pad23)") (class "Default")
      (node (ref "X1") (pin "23") (pinfunction "1_23") (pintype "passive"))
    )
  )
)
